# csa-ultrabus-1_0a.net
KiCad netlist of a schematic drawn in EAGLE
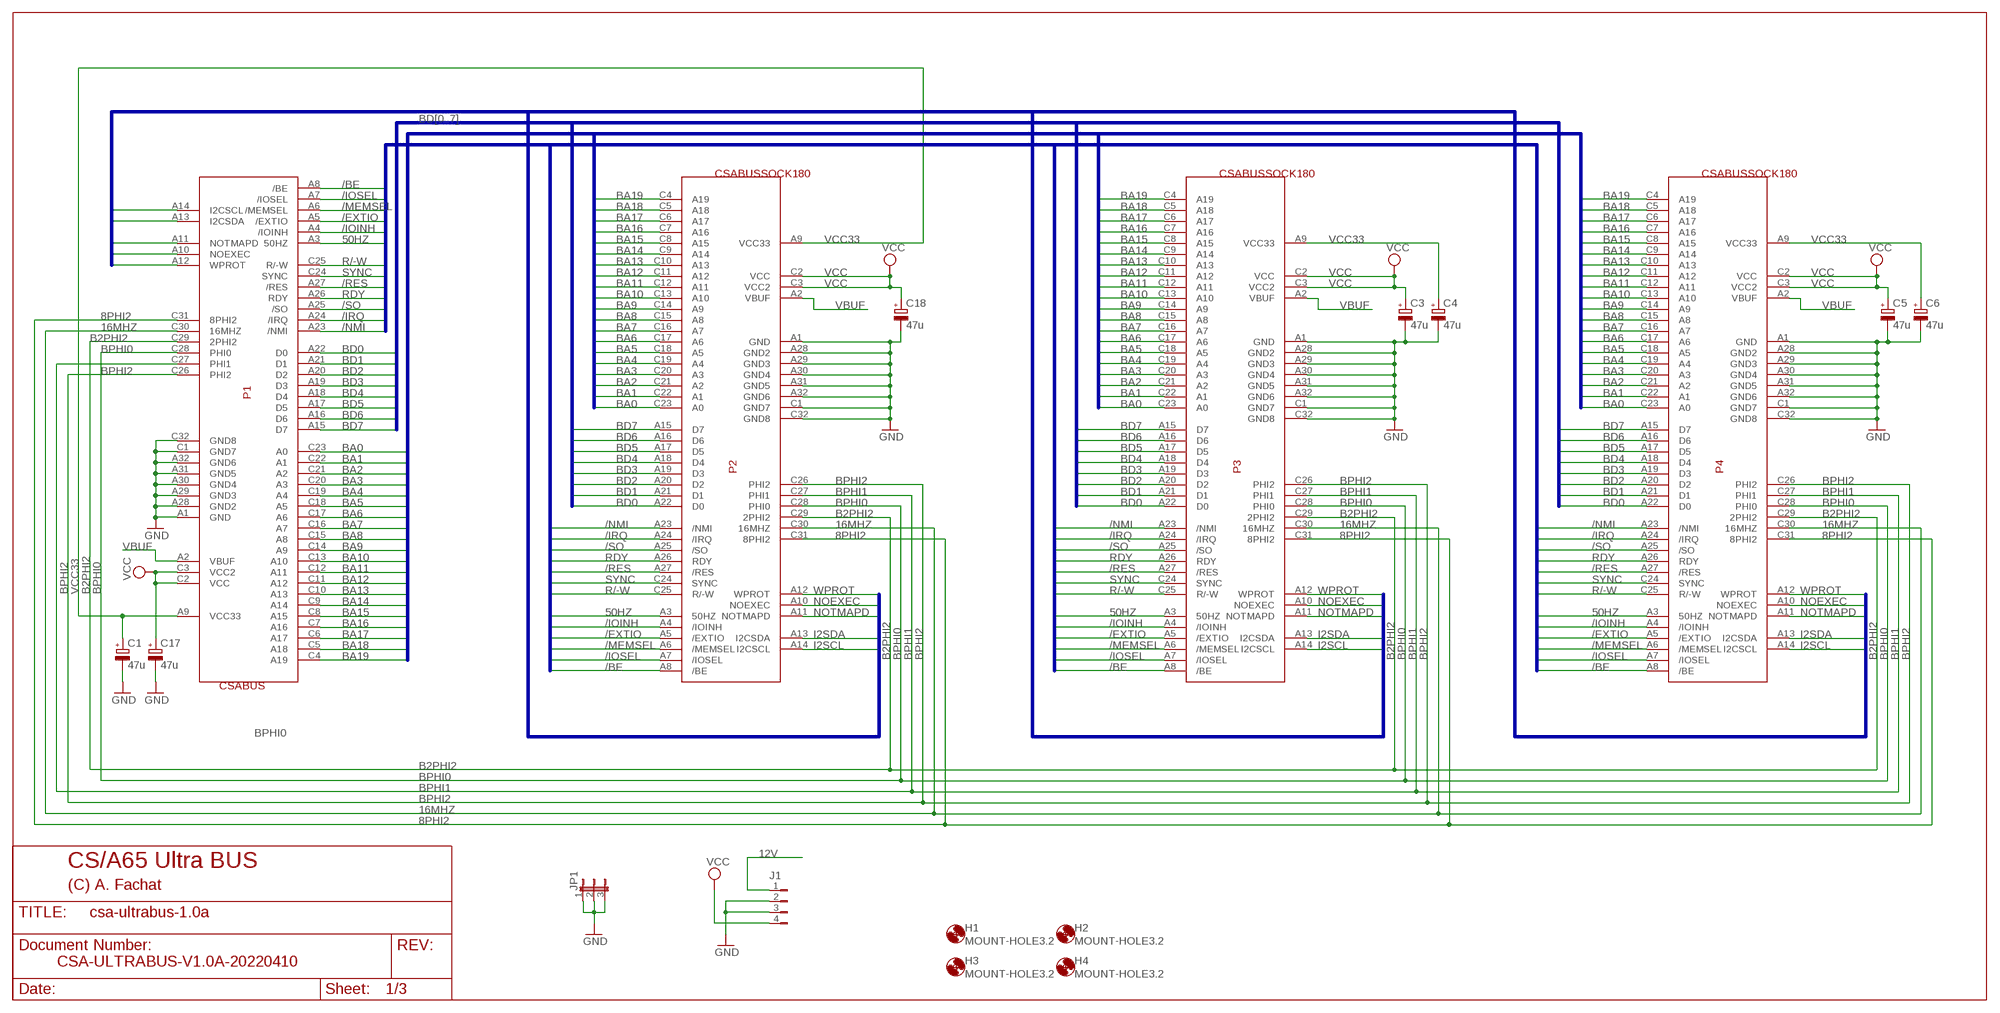
[diagram p0: schematic, sheet 1]
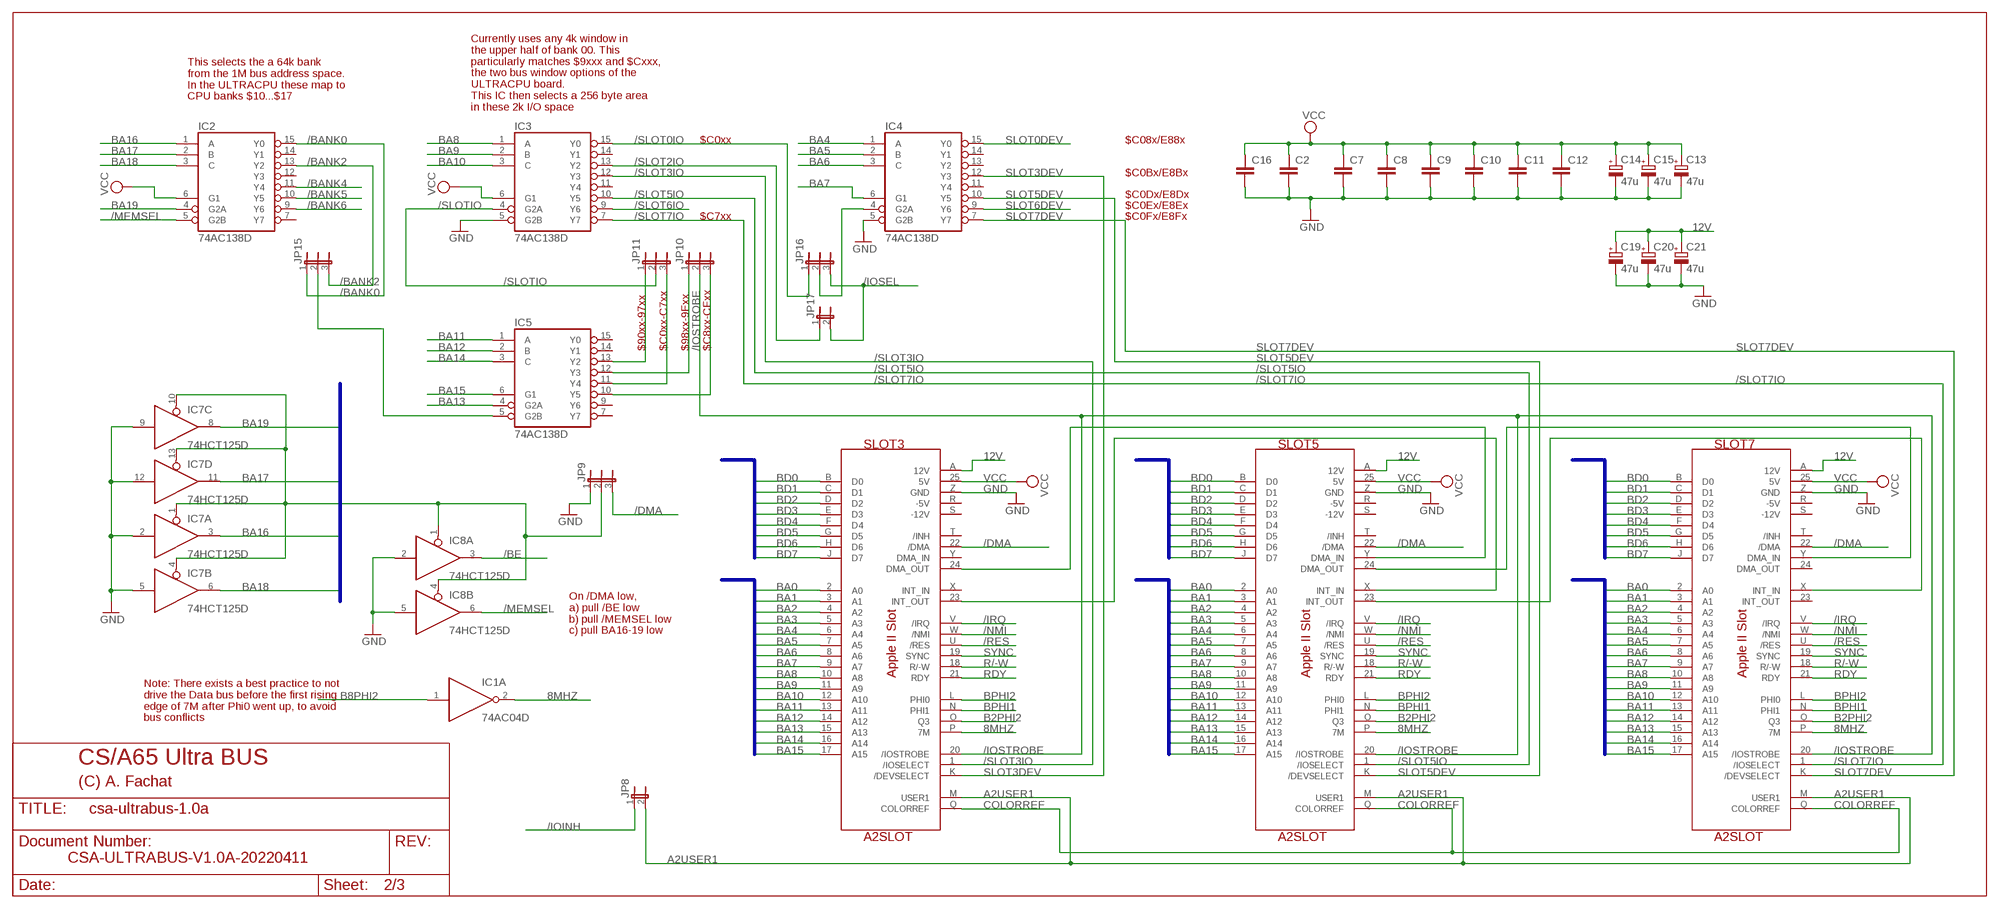
[diagram p1: schematic, sheet 2]
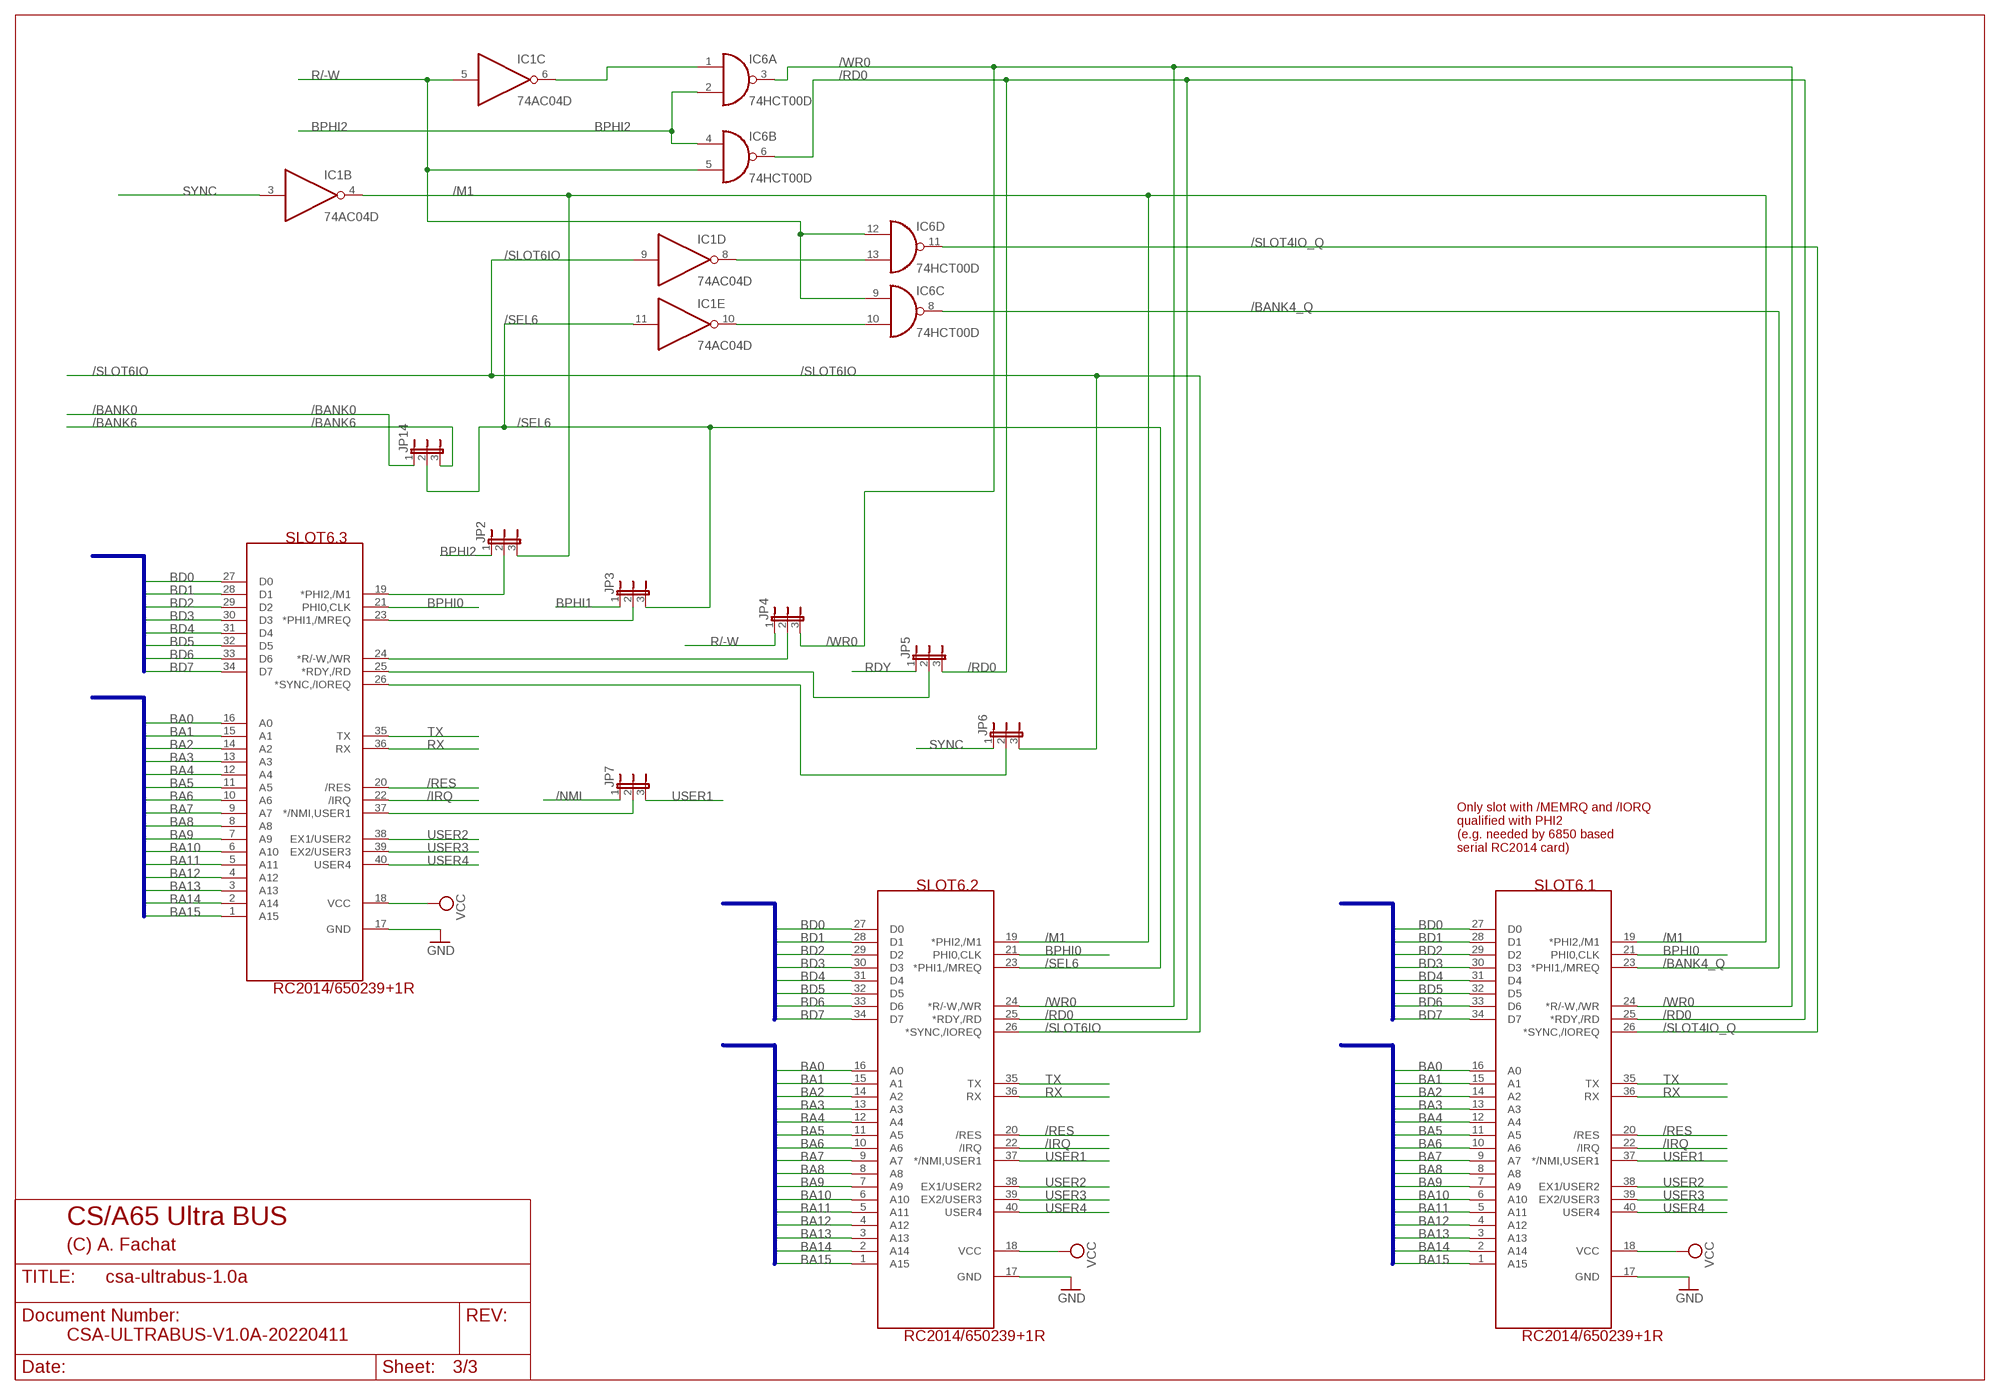
[diagram p2: schematic, sheet 3]

(export (version "E")
  (design (tool "Eeschema 10.0.6"))
  (components
    (comp (ref "C2")
      (value "C-EUC0603")
      (footprint "eagle-import:C0603")
      (libsource (lib "eagle-import") (part "C-EUC0603"))
    )
    (comp (ref "C7")
      (value "C-EUC0603")
      (footprint "eagle-import:C0603")
      (libsource (lib "eagle-import") (part "C-EUC0603"))
    )
    (comp (ref "C8")
      (value "C-EUC0603")
      (footprint "eagle-import:C0603")
      (libsource (lib "eagle-import") (part "C-EUC0603"))
    )
    (comp (ref "C9")
      (value "C-EUC0603")
      (footprint "eagle-import:C0603")
      (libsource (lib "eagle-import") (part "C-EUC0603"))
    )
    (comp (ref "C10")
      (value "C-EUC0603")
      (footprint "eagle-import:C0603")
      (libsource (lib "eagle-import") (part "C-EUC0603"))
    )
    (comp (ref "C11")
      (value "C-EUC0603")
      (footprint "eagle-import:C0603")
      (libsource (lib "eagle-import") (part "C-EUC0603"))
    )
    (comp (ref "C12")
      (value "C-EUC0603")
      (footprint "eagle-import:C0603")
      (libsource (lib "eagle-import") (part "C-EUC0603"))
    )
    (comp (ref "C13")
      (value "47u")
      (footprint "eagle-import:E2,5-5")
      (libsource (lib "eagle-import") (part "CPOL-EUE2.5-5"))
    )
    (comp (ref "C14")
      (value "47u")
      (footprint "eagle-import:E2,5-5")
      (libsource (lib "eagle-import") (part "CPOL-EUE2.5-5"))
    )
    (comp (ref "C15")
      (value "47u")
      (footprint "eagle-import:E2,5-5")
      (libsource (lib "eagle-import") (part "CPOL-EUE2.5-5"))
    )
    (comp (ref "C16")
      (value "C-EUC0603")
      (footprint "eagle-import:C0603")
      (libsource (lib "eagle-import") (part "C-EUC0603"))
    )
    (comp (ref "C19")
      (value "47u")
      (footprint "eagle-import:E2,5-5")
      (libsource (lib "eagle-import") (part "CPOL-EUE2.5-5"))
    )
    (comp (ref "C20")
      (value "47u")
      (footprint "eagle-import:E2,5-5")
      (libsource (lib "eagle-import") (part "CPOL-EUE2.5-5"))
    )
    (comp (ref "C21")
      (value "47u")
      (footprint "eagle-import:E2,5-5")
      (libsource (lib "eagle-import") (part "CPOL-EUE2.5-5"))
    )
    (comp (ref "IC1")
      (value "74AC04D")
      (footprint "eagle-import:SO14")
      (libsource (lib "eagle-import") (part "7404DAC"))
    )
    (comp (ref "IC2")
      (value "74AC138D")
      (footprint "eagle-import:SO16")
      (libsource (lib "eagle-import") (part "74138DAC"))
    )
    (comp (ref "IC3")
      (value "74AC138D")
      (footprint "eagle-import:SO16")
      (libsource (lib "eagle-import") (part "74138DAC"))
    )
    (comp (ref "IC4")
      (value "74AC138D")
      (footprint "eagle-import:SO16")
      (libsource (lib "eagle-import") (part "74138DAC"))
    )
    (comp (ref "IC5")
      (value "74AC138D")
      (footprint "eagle-import:SO16")
      (libsource (lib "eagle-import") (part "74138DAC"))
    )
    (comp (ref "IC7")
      (value "74HCT125D")
      (footprint "eagle-import:SO14")
      (libsource (lib "eagle-import") (part "74125DHCT"))
    )
    (comp (ref "IC8")
      (value "74HCT125D")
      (footprint "eagle-import:SO14")
      (libsource (lib "eagle-import") (part "74125DHCT"))
    )
    (comp (ref "JP8")
      (value "JP1E")
      (footprint "eagle-import:JP1")
      (libsource (lib "eagle-import") (part "JP1E"))
    )
    (comp (ref "JP9")
      (value "JP2E")
      (footprint "eagle-import:JP2")
      (libsource (lib "eagle-import") (part "JP2E"))
    )
    (comp (ref "JP10")
      (value "JP2E")
      (footprint "eagle-import:JP2")
      (libsource (lib "eagle-import") (part "JP2E"))
    )
    (comp (ref "JP11")
      (value "JP2E")
      (footprint "eagle-import:JP2")
      (libsource (lib "eagle-import") (part "JP2E"))
    )
    (comp (ref "JP15")
      (value "JP2E")
      (footprint "eagle-import:JP2")
      (libsource (lib "eagle-import") (part "JP2E"))
    )
    (comp (ref "JP16")
      (value "JP2E")
      (footprint "eagle-import:JP2")
      (libsource (lib "eagle-import") (part "JP2E"))
    )
    (comp (ref "JP17")
      (value "JP1E")
      (footprint "eagle-import:JP1")
      (libsource (lib "eagle-import") (part "JP1E"))
    )
    (comp (ref "SLOT3")
      (value "A2SLOT")
      (footprint "eagle-import:FE100-25")
      (libsource (lib "eagle-import") (part "A2SLOT"))
    )
    (comp (ref "SLOT5")
      (value "A2SLOT")
      (footprint "eagle-import:FE100-25")
      (libsource (lib "eagle-import") (part "A2SLOT"))
    )
    (comp (ref "SLOT7")
      (value "A2SLOT")
      (footprint "eagle-import:FE100-25")
      (libsource (lib "eagle-import") (part "A2SLOT"))
    )
    (comp (ref "IC6")
      (value "74HCT00D")
      (footprint "eagle-import:SO14")
      (libsource (lib "eagle-import") (part "7400DHCT"))
    )
    (comp (ref "JP2")
      (value "JP2E")
      (footprint "eagle-import:JP2")
      (libsource (lib "eagle-import") (part "JP2E"))
    )
    (comp (ref "JP3")
      (value "JP2E")
      (footprint "eagle-import:JP2")
      (libsource (lib "eagle-import") (part "JP2E"))
    )
    (comp (ref "JP4")
      (value "JP2E")
      (footprint "eagle-import:JP2")
      (libsource (lib "eagle-import") (part "JP2E"))
    )
    (comp (ref "JP5")
      (value "JP2E")
      (footprint "eagle-import:JP2")
      (libsource (lib "eagle-import") (part "JP2E"))
    )
    (comp (ref "JP6")
      (value "JP2E")
      (footprint "eagle-import:JP2")
      (libsource (lib "eagle-import") (part "JP2E"))
    )
    (comp (ref "JP7")
      (value "JP2E")
      (footprint "eagle-import:JP2")
      (libsource (lib "eagle-import") (part "JP2E"))
    )
    (comp (ref "JP14")
      (value "JP2E")
      (footprint "eagle-import:JP2")
      (libsource (lib "eagle-import") (part "JP2E"))
    )
    (comp (ref "SLOT6.1")
      (value "RC2014/650239+1R")
      (footprint "eagle-import:SIL39+1R")
      (libsource (lib "eagle-import") (part "RC2014/650239+1R"))
    )
    (comp (ref "SLOT6.2")
      (value "RC2014/650239+1R")
      (footprint "eagle-import:SIL39+1R")
      (libsource (lib "eagle-import") (part "RC2014/650239+1R"))
    )
    (comp (ref "SLOT6.3")
      (value "RC2014/650239+1R")
      (footprint "eagle-import:SIL39+1R")
      (libsource (lib "eagle-import") (part "RC2014/650239+1R"))
    )
    (comp (ref "C1")
      (value "47u")
      (footprint "eagle-import:E2,5-5")
      (libsource (lib "eagle-import") (part "CPOL-EUE2.5-5"))
    )
    (comp (ref "C3")
      (value "47u")
      (footprint "eagle-import:E2,5-5")
      (libsource (lib "eagle-import") (part "CPOL-EUE2.5-5"))
    )
    (comp (ref "C4")
      (value "47u")
      (footprint "eagle-import:E2,5-5")
      (libsource (lib "eagle-import") (part "CPOL-EUE2.5-5"))
    )
    (comp (ref "C5")
      (value "47u")
      (footprint "eagle-import:E2,5-5")
      (libsource (lib "eagle-import") (part "CPOL-EUE2.5-5"))
    )
    (comp (ref "C6")
      (value "47u")
      (footprint "eagle-import:E2,5-5")
      (libsource (lib "eagle-import") (part "CPOL-EUE2.5-5"))
    )
    (comp (ref "C17")
      (value "47u")
      (footprint "eagle-import:E2,5-5")
      (libsource (lib "eagle-import") (part "CPOL-EUE2.5-5"))
    )
    (comp (ref "C18")
      (value "47u")
      (footprint "eagle-import:E2,5-5")
      (libsource (lib "eagle-import") (part "CPOL-EUE2.5-5"))
    )
    (comp (ref "H1")
      (value "MOUNT-HOLE3.2")
      (footprint "eagle-import:3,2")
      (libsource (lib "eagle-import") (part "MOUNT-HOLE3.2"))
    )
    (comp (ref "H2")
      (value "MOUNT-HOLE3.2")
      (footprint "eagle-import:3,2")
      (libsource (lib "eagle-import") (part "MOUNT-HOLE3.2"))
    )
    (comp (ref "H3")
      (value "MOUNT-HOLE3.2")
      (footprint "eagle-import:3,2")
      (libsource (lib "eagle-import") (part "MOUNT-HOLE3.2"))
    )
    (comp (ref "H4")
      (value "MOUNT-HOLE3.2")
      (footprint "eagle-import:3,2")
      (libsource (lib "eagle-import") (part "MOUNT-HOLE3.2"))
    )
    (comp (ref "J1")
      (value "FLOP-4W827001")
      (footprint "eagle-import:827001")
      (libsource (lib "eagle-import") (part "FLOP-4W827001"))
    )
    (comp (ref "JP1")
      (value "JP2E")
      (footprint "eagle-import:JP2")
      (libsource (lib "eagle-import") (part "JP2E"))
    )
    (comp (ref "P1")
      (value "CSABUS")
      (footprint "eagle-import:CSABUS")
      (libsource (lib "eagle-import") (part "CSABUS"))
    )
    (comp (ref "P2")
      (value "CSABUSSOCK180")
      (footprint "eagle-import:CSABUSSOCK180")
      (libsource (lib "eagle-import") (part "CSABUSSOCK180"))
    )
    (comp (ref "P3")
      (value "CSABUSSOCK180")
      (footprint "eagle-import:CSABUSSOCK180")
      (libsource (lib "eagle-import") (part "CSABUSSOCK180"))
    )
    (comp (ref "P4")
      (value "CSABUSSOCK180")
      (footprint "eagle-import:CSABUSSOCK180")
      (libsource (lib "eagle-import") (part "CSABUSSOCK180"))
    )
  )
  (nets
    (net (code "6") (name "8MHZ") (class "Default")
      (node (ref "IC1") (pin "2") (pinfunction "O_2") (pintype "output"))
      (node (ref "SLOT3") (pin "P") (pinfunction "7M_P") (pintype "bidirectional"))
      (node (ref "SLOT5") (pin "P") (pinfunction "7M_P") (pintype "bidirectional"))
      (node (ref "SLOT7") (pin "P") (pinfunction "7M_P") (pintype "bidirectional"))
    )
    (net (code "7") (name "8PHI2") (class "Default")
      (node (ref "P1") (pin "C31") (pinfunction "8PHI2_C31") (pintype "bidirectional"))
      (node (ref "P2") (pin "C31") (pinfunction "8PHI2_C31") (pintype "bidirectional"))
      (node (ref "P3") (pin "C31") (pinfunction "8PHI2_C31") (pintype "bidirectional"))
      (node (ref "P4") (pin "C31") (pinfunction "8PHI2_C31") (pintype "bidirectional"))
    )
    (net (code "8") (name "12V") (class "Default")
      (node (ref "C19") (pin "+") (pinfunction "+_+") (pintype "passive"))
      (node (ref "C20") (pin "+") (pinfunction "+_+") (pintype "passive"))
      (node (ref "C21") (pin "+") (pinfunction "+_+") (pintype "passive"))
      (node (ref "J1") (pin "1") (pinfunction "1_1") (pintype "passive"))
      (node (ref "SLOT3") (pin "A") (pinfunction "12V_A") (pintype "bidirectional"))
      (node (ref "SLOT5") (pin "A") (pinfunction "12V_A") (pintype "bidirectional"))
      (node (ref "SLOT7") (pin "A") (pinfunction "12V_A") (pintype "bidirectional"))
    )
    (net (code "9") (name "16MHZ") (class "Default")
      (node (ref "P1") (pin "C30") (pinfunction "16MHZ_C30") (pintype "bidirectional"))
      (node (ref "P2") (pin "C30") (pinfunction "16MHZ_C30") (pintype "bidirectional"))
      (node (ref "P3") (pin "C30") (pinfunction "16MHZ_C30") (pintype "bidirectional"))
      (node (ref "P4") (pin "C30") (pinfunction "16MHZ_C30") (pintype "bidirectional"))
    )
    (net (code "10") (name "50HZ") (class "Default")
      (node (ref "P1") (pin "A3") (pinfunction "50HZ_A3") (pintype "bidirectional"))
      (node (ref "P2") (pin "A3") (pinfunction "50HZ_A3") (pintype "bidirectional"))
      (node (ref "P3") (pin "A3") (pinfunction "50HZ_A3") (pintype "bidirectional"))
      (node (ref "P4") (pin "A3") (pinfunction "50HZ_A3") (pintype "bidirectional"))
    )
    (net (code "11") (name "A2USER1") (class "Default")
      (node (ref "JP8") (pin "2") (pinfunction "2_2") (pintype "passive"))
      (node (ref "SLOT3") (pin "M") (pinfunction "USER1_M") (pintype "bidirectional"))
      (node (ref "SLOT5") (pin "M") (pinfunction "USER1_M") (pintype "bidirectional"))
      (node (ref "SLOT7") (pin "M") (pinfunction "USER1_M") (pintype "bidirectional"))
    )
    (net (code "12") (name "B2PHI2") (class "Default")
      (node (ref "P1") (pin "C29") (pinfunction "2PHI2_C29") (pintype "bidirectional"))
      (node (ref "P2") (pin "C29") (pinfunction "2PHI2_C29") (pintype "bidirectional"))
      (node (ref "P3") (pin "C29") (pinfunction "2PHI2_C29") (pintype "bidirectional"))
      (node (ref "P4") (pin "C29") (pinfunction "2PHI2_C29") (pintype "bidirectional"))
      (node (ref "SLOT3") (pin "O") (pinfunction "Q3_O") (pintype "bidirectional"))
      (node (ref "SLOT5") (pin "O") (pinfunction "Q3_O") (pintype "bidirectional"))
      (node (ref "SLOT7") (pin "O") (pinfunction "Q3_O") (pintype "bidirectional"))
    )
    (net (code "13") (name "B8PHI2") (class "Default")
      (node (ref "IC1") (pin "1") (pinfunction "I_1") (pintype "input"))
    )
    (net (code "14") (name "BA0") (class "Default")
      (node (ref "P1") (pin "C23") (pinfunction "A0_C23") (pintype "bidirectional"))
      (node (ref "P2") (pin "C23") (pinfunction "A0_C23") (pintype "bidirectional"))
      (node (ref "P3") (pin "C23") (pinfunction "A0_C23") (pintype "bidirectional"))
      (node (ref "P4") (pin "C23") (pinfunction "A0_C23") (pintype "bidirectional"))
      (node (ref "SLOT3") (pin "2") (pinfunction "A0_2") (pintype "bidirectional"))
      (node (ref "SLOT5") (pin "2") (pinfunction "A0_2") (pintype "bidirectional"))
      (node (ref "SLOT6.1") (pin "16") (pinfunction "A0_16") (pintype "bidirectional"))
      (node (ref "SLOT6.2") (pin "16") (pinfunction "A0_16") (pintype "bidirectional"))
      (node (ref "SLOT6.3") (pin "16") (pinfunction "A0_16") (pintype "bidirectional"))
      (node (ref "SLOT7") (pin "2") (pinfunction "A0_2") (pintype "bidirectional"))
    )
    (net (code "15") (name "BA1") (class "Default")
      (node (ref "P1") (pin "C22") (pinfunction "A1_C22") (pintype "bidirectional"))
      (node (ref "P2") (pin "C22") (pinfunction "A1_C22") (pintype "bidirectional"))
      (node (ref "P3") (pin "C22") (pinfunction "A1_C22") (pintype "bidirectional"))
      (node (ref "P4") (pin "C22") (pinfunction "A1_C22") (pintype "bidirectional"))
      (node (ref "SLOT3") (pin "3") (pinfunction "A1_3") (pintype "bidirectional"))
      (node (ref "SLOT5") (pin "3") (pinfunction "A1_3") (pintype "bidirectional"))
      (node (ref "SLOT6.1") (pin "15") (pinfunction "A1_15") (pintype "bidirectional"))
      (node (ref "SLOT6.2") (pin "15") (pinfunction "A1_15") (pintype "bidirectional"))
      (node (ref "SLOT6.3") (pin "15") (pinfunction "A1_15") (pintype "bidirectional"))
      (node (ref "SLOT7") (pin "3") (pinfunction "A1_3") (pintype "bidirectional"))
    )
    (net (code "16") (name "BA2") (class "Default")
      (node (ref "P1") (pin "C21") (pinfunction "A2_C21") (pintype "bidirectional"))
      (node (ref "P2") (pin "C21") (pinfunction "A2_C21") (pintype "bidirectional"))
      (node (ref "P3") (pin "C21") (pinfunction "A2_C21") (pintype "bidirectional"))
      (node (ref "P4") (pin "C21") (pinfunction "A2_C21") (pintype "bidirectional"))
      (node (ref "SLOT3") (pin "4") (pinfunction "A2_4") (pintype "bidirectional"))
      (node (ref "SLOT5") (pin "4") (pinfunction "A2_4") (pintype "bidirectional"))
      (node (ref "SLOT6.1") (pin "14") (pinfunction "A2_14") (pintype "bidirectional"))
      (node (ref "SLOT6.2") (pin "14") (pinfunction "A2_14") (pintype "bidirectional"))
      (node (ref "SLOT6.3") (pin "14") (pinfunction "A2_14") (pintype "bidirectional"))
      (node (ref "SLOT7") (pin "4") (pinfunction "A2_4") (pintype "bidirectional"))
    )
    (net (code "17") (name "BA3") (class "Default")
      (node (ref "P1") (pin "C20") (pinfunction "A3_C20") (pintype "bidirectional"))
      (node (ref "P2") (pin "C20") (pinfunction "A3_C20") (pintype "bidirectional"))
      (node (ref "P3") (pin "C20") (pinfunction "A3_C20") (pintype "bidirectional"))
      (node (ref "P4") (pin "C20") (pinfunction "A3_C20") (pintype "bidirectional"))
      (node (ref "SLOT3") (pin "5") (pinfunction "A3_5") (pintype "bidirectional"))
      (node (ref "SLOT5") (pin "5") (pinfunction "A3_5") (pintype "bidirectional"))
      (node (ref "SLOT6.1") (pin "13") (pinfunction "A3_13") (pintype "bidirectional"))
      (node (ref "SLOT6.2") (pin "13") (pinfunction "A3_13") (pintype "bidirectional"))
      (node (ref "SLOT6.3") (pin "13") (pinfunction "A3_13") (pintype "bidirectional"))
      (node (ref "SLOT7") (pin "5") (pinfunction "A3_5") (pintype "bidirectional"))
    )
    (net (code "18") (name "BA4") (class "Default")
      (node (ref "IC4") (pin "1") (pinfunction "A_1") (pintype "input"))
      (node (ref "P1") (pin "C19") (pinfunction "A4_C19") (pintype "bidirectional"))
      (node (ref "P2") (pin "C19") (pinfunction "A4_C19") (pintype "bidirectional"))
      (node (ref "P3") (pin "C19") (pinfunction "A4_C19") (pintype "bidirectional"))
      (node (ref "P4") (pin "C19") (pinfunction "A4_C19") (pintype "bidirectional"))
      (node (ref "SLOT3") (pin "6") (pinfunction "A4_6") (pintype "bidirectional"))
      (node (ref "SLOT5") (pin "6") (pinfunction "A4_6") (pintype "bidirectional"))
      (node (ref "SLOT6.1") (pin "12") (pinfunction "A4_12") (pintype "bidirectional"))
      (node (ref "SLOT6.2") (pin "12") (pinfunction "A4_12") (pintype "bidirectional"))
      (node (ref "SLOT6.3") (pin "12") (pinfunction "A4_12") (pintype "bidirectional"))
      (node (ref "SLOT7") (pin "6") (pinfunction "A4_6") (pintype "bidirectional"))
    )
    (net (code "19") (name "BA5") (class "Default")
      (node (ref "IC4") (pin "2") (pinfunction "B_2") (pintype "input"))
      (node (ref "P1") (pin "C18") (pinfunction "A5_C18") (pintype "bidirectional"))
      (node (ref "P2") (pin "C18") (pinfunction "A5_C18") (pintype "bidirectional"))
      (node (ref "P3") (pin "C18") (pinfunction "A5_C18") (pintype "bidirectional"))
      (node (ref "P4") (pin "C18") (pinfunction "A5_C18") (pintype "bidirectional"))
      (node (ref "SLOT3") (pin "7") (pinfunction "A5_7") (pintype "bidirectional"))
      (node (ref "SLOT5") (pin "7") (pinfunction "A5_7") (pintype "bidirectional"))
      (node (ref "SLOT6.1") (pin "11") (pinfunction "A5_11") (pintype "bidirectional"))
      (node (ref "SLOT6.2") (pin "11") (pinfunction "A5_11") (pintype "bidirectional"))
      (node (ref "SLOT6.3") (pin "11") (pinfunction "A5_11") (pintype "bidirectional"))
      (node (ref "SLOT7") (pin "7") (pinfunction "A5_7") (pintype "bidirectional"))
    )
    (net (code "20") (name "BA6") (class "Default")
      (node (ref "IC4") (pin "3") (pinfunction "C_3") (pintype "input"))
      (node (ref "P1") (pin "C17") (pinfunction "A6_C17") (pintype "bidirectional"))
      (node (ref "P2") (pin "C17") (pinfunction "A6_C17") (pintype "bidirectional"))
      (node (ref "P3") (pin "C17") (pinfunction "A6_C17") (pintype "bidirectional"))
      (node (ref "P4") (pin "C17") (pinfunction "A6_C17") (pintype "bidirectional"))
      (node (ref "SLOT3") (pin "8") (pinfunction "A6_8") (pintype "bidirectional"))
      (node (ref "SLOT5") (pin "8") (pinfunction "A6_8") (pintype "bidirectional"))
      (node (ref "SLOT6.1") (pin "10") (pinfunction "A6_10") (pintype "bidirectional"))
      (node (ref "SLOT6.2") (pin "10") (pinfunction "A6_10") (pintype "bidirectional"))
      (node (ref "SLOT6.3") (pin "10") (pinfunction "A6_10") (pintype "bidirectional"))
      (node (ref "SLOT7") (pin "8") (pinfunction "A6_8") (pintype "bidirectional"))
    )
    (net (code "21") (name "BA7") (class "Default")
      (node (ref "IC4") (pin "6") (pinfunction "G1_6") (pintype "input"))
      (node (ref "P1") (pin "C16") (pinfunction "A7_C16") (pintype "bidirectional"))
      (node (ref "P2") (pin "C16") (pinfunction "A7_C16") (pintype "bidirectional"))
      (node (ref "P3") (pin "C16") (pinfunction "A7_C16") (pintype "bidirectional"))
      (node (ref "P4") (pin "C16") (pinfunction "A7_C16") (pintype "bidirectional"))
      (node (ref "SLOT3") (pin "9") (pinfunction "A7_9") (pintype "bidirectional"))
      (node (ref "SLOT5") (pin "9") (pinfunction "A7_9") (pintype "bidirectional"))
      (node (ref "SLOT6.1") (pin "9") (pinfunction "A7_9") (pintype "bidirectional"))
      (node (ref "SLOT6.2") (pin "9") (pinfunction "A7_9") (pintype "bidirectional"))
      (node (ref "SLOT6.3") (pin "9") (pinfunction "A7_9") (pintype "bidirectional"))
      (node (ref "SLOT7") (pin "9") (pinfunction "A7_9") (pintype "bidirectional"))
    )
    (net (code "22") (name "BA8") (class "Default")
      (node (ref "IC3") (pin "1") (pinfunction "A_1") (pintype "input"))
      (node (ref "P1") (pin "C15") (pinfunction "A8_C15") (pintype "bidirectional"))
      (node (ref "P2") (pin "C15") (pinfunction "A8_C15") (pintype "bidirectional"))
      (node (ref "P3") (pin "C15") (pinfunction "A8_C15") (pintype "bidirectional"))
      (node (ref "P4") (pin "C15") (pinfunction "A8_C15") (pintype "bidirectional"))
      (node (ref "SLOT3") (pin "10") (pinfunction "A8_10") (pintype "bidirectional"))
      (node (ref "SLOT5") (pin "10") (pinfunction "A8_10") (pintype "bidirectional"))
      (node (ref "SLOT6.1") (pin "8") (pinfunction "A8_8") (pintype "bidirectional"))
      (node (ref "SLOT6.2") (pin "8") (pinfunction "A8_8") (pintype "bidirectional"))
      (node (ref "SLOT6.3") (pin "8") (pinfunction "A8_8") (pintype "bidirectional"))
      (node (ref "SLOT7") (pin "10") (pinfunction "A8_10") (pintype "bidirectional"))
    )
    (net (code "23") (name "BA9") (class "Default")
      (node (ref "IC3") (pin "2") (pinfunction "B_2") (pintype "input"))
      (node (ref "P1") (pin "C14") (pinfunction "A9_C14") (pintype "bidirectional"))
      (node (ref "P2") (pin "C14") (pinfunction "A9_C14") (pintype "bidirectional"))
      (node (ref "P3") (pin "C14") (pinfunction "A9_C14") (pintype "bidirectional"))
      (node (ref "P4") (pin "C14") (pinfunction "A9_C14") (pintype "bidirectional"))
      (node (ref "SLOT3") (pin "11") (pinfunction "A9_11") (pintype "bidirectional"))
      (node (ref "SLOT5") (pin "11") (pinfunction "A9_11") (pintype "bidirectional"))
      (node (ref "SLOT6.1") (pin "7") (pinfunction "A9_7") (pintype "bidirectional"))
      (node (ref "SLOT6.2") (pin "7") (pinfunction "A9_7") (pintype "bidirectional"))
      (node (ref "SLOT6.3") (pin "7") (pinfunction "A9_7") (pintype "bidirectional"))
      (node (ref "SLOT7") (pin "11") (pinfunction "A9_11") (pintype "bidirectional"))
    )
    (net (code "24") (name "BA10") (class "Default")
      (node (ref "IC3") (pin "3") (pinfunction "C_3") (pintype "input"))
      (node (ref "P1") (pin "C13") (pinfunction "A10_C13") (pintype "bidirectional"))
      (node (ref "P2") (pin "C13") (pinfunction "A10_C13") (pintype "bidirectional"))
      (node (ref "P3") (pin "C13") (pinfunction "A10_C13") (pintype "bidirectional"))
      (node (ref "P4") (pin "C13") (pinfunction "A10_C13") (pintype "bidirectional"))
      (node (ref "SLOT3") (pin "12") (pinfunction "A10_12") (pintype "bidirectional"))
      (node (ref "SLOT5") (pin "12") (pinfunction "A10_12") (pintype "bidirectional"))
      (node (ref "SLOT6.1") (pin "6") (pinfunction "A10_6") (pintype "bidirectional"))
      (node (ref "SLOT6.2") (pin "6") (pinfunction "A10_6") (pintype "bidirectional"))
      (node (ref "SLOT6.3") (pin "6") (pinfunction "A10_6") (pintype "bidirectional"))
      (node (ref "SLOT7") (pin "12") (pinfunction "A10_12") (pintype "bidirectional"))
    )
    (net (code "25") (name "BA11") (class "Default")
      (node (ref "IC5") (pin "1") (pinfunction "A_1") (pintype "input"))
      (node (ref "P1") (pin "C12") (pinfunction "A11_C12") (pintype "bidirectional"))
      (node (ref "P2") (pin "C12") (pinfunction "A11_C12") (pintype "bidirectional"))
      (node (ref "P3") (pin "C12") (pinfunction "A11_C12") (pintype "bidirectional"))
      (node (ref "P4") (pin "C12") (pinfunction "A11_C12") (pintype "bidirectional"))
      (node (ref "SLOT3") (pin "13") (pinfunction "A11_13") (pintype "bidirectional"))
      (node (ref "SLOT5") (pin "13") (pinfunction "A11_13") (pintype "bidirectional"))
      (node (ref "SLOT6.1") (pin "5") (pinfunction "A11_5") (pintype "bidirectional"))
      (node (ref "SLOT6.2") (pin "5") (pinfunction "A11_5") (pintype "bidirectional"))
      (node (ref "SLOT6.3") (pin "5") (pinfunction "A11_5") (pintype "bidirectional"))
      (node (ref "SLOT7") (pin "13") (pinfunction "A11_13") (pintype "bidirectional"))
    )
    (net (code "26") (name "BA12") (class "Default")
      (node (ref "IC5") (pin "2") (pinfunction "B_2") (pintype "input"))
      (node (ref "P1") (pin "C11") (pinfunction "A12_C11") (pintype "bidirectional"))
      (node (ref "P2") (pin "C11") (pinfunction "A12_C11") (pintype "bidirectional"))
      (node (ref "P3") (pin "C11") (pinfunction "A12_C11") (pintype "bidirectional"))
      (node (ref "P4") (pin "C11") (pinfunction "A12_C11") (pintype "bidirectional"))
      (node (ref "SLOT3") (pin "14") (pinfunction "A12_14") (pintype "bidirectional"))
      (node (ref "SLOT5") (pin "14") (pinfunction "A12_14") (pintype "bidirectional"))
      (node (ref "SLOT6.1") (pin "4") (pinfunction "A12_4") (pintype "bidirectional"))
      (node (ref "SLOT6.2") (pin "4") (pinfunction "A12_4") (pintype "bidirectional"))
      (node (ref "SLOT6.3") (pin "4") (pinfunction "A12_4") (pintype "bidirectional"))
      (node (ref "SLOT7") (pin "14") (pinfunction "A12_14") (pintype "bidirectional"))
    )
    (net (code "27") (name "BA13") (class "Default")
      (node (ref "IC5") (pin "4") (pinfunction "G2A_4") (pintype "input"))
      (node (ref "P1") (pin "C10") (pinfunction "A13_C10") (pintype "bidirectional"))
      (node (ref "P2") (pin "C10") (pinfunction "A13_C10") (pintype "bidirectional"))
      (node (ref "P3") (pin "C10") (pinfunction "A13_C10") (pintype "bidirectional"))
      (node (ref "P4") (pin "C10") (pinfunction "A13_C10") (pintype "bidirectional"))
      (node (ref "SLOT3") (pin "15") (pinfunction "A13_15") (pintype "bidirectional"))
      (node (ref "SLOT5") (pin "15") (pinfunction "A13_15") (pintype "bidirectional"))
      (node (ref "SLOT6.1") (pin "3") (pinfunction "A13_3") (pintype "bidirectional"))
      (node (ref "SLOT6.2") (pin "3") (pinfunction "A13_3") (pintype "bidirectional"))
      (node (ref "SLOT6.3") (pin "3") (pinfunction "A13_3") (pintype "bidirectional"))
      (node (ref "SLOT7") (pin "15") (pinfunction "A13_15") (pintype "bidirectional"))
    )
    (net (code "28") (name "BA14") (class "Default")
      (node (ref "IC5") (pin "3") (pinfunction "C_3") (pintype "input"))
      (node (ref "P1") (pin "C9") (pinfunction "A14_C9") (pintype "bidirectional"))
      (node (ref "P2") (pin "C9") (pinfunction "A14_C9") (pintype "bidirectional"))
      (node (ref "P3") (pin "C9") (pinfunction "A14_C9") (pintype "bidirectional"))
      (node (ref "P4") (pin "C9") (pinfunction "A14_C9") (pintype "bidirectional"))
      (node (ref "SLOT3") (pin "16") (pinfunction "A14_16") (pintype "bidirectional"))
      (node (ref "SLOT5") (pin "16") (pinfunction "A14_16") (pintype "bidirectional"))
      (node (ref "SLOT6.1") (pin "2") (pinfunction "A14_2") (pintype "bidirectional"))
      (node (ref "SLOT6.2") (pin "2") (pinfunction "A14_2") (pintype "bidirectional"))
      (node (ref "SLOT6.3") (pin "2") (pinfunction "A14_2") (pintype "bidirectional"))
      (node (ref "SLOT7") (pin "16") (pinfunction "A14_16") (pintype "bidirectional"))
    )
    (net (code "29") (name "BA15") (class "Default")
      (node (ref "IC5") (pin "6") (pinfunction "G1_6") (pintype "input"))
      (node (ref "P1") (pin "C8") (pinfunction "A15_C8") (pintype "bidirectional"))
      (node (ref "P2") (pin "C8") (pinfunction "A15_C8") (pintype "bidirectional"))
      (node (ref "P3") (pin "C8") (pinfunction "A15_C8") (pintype "bidirectional"))
      (node (ref "P4") (pin "C8") (pinfunction "A15_C8") (pintype "bidirectional"))
      (node (ref "SLOT3") (pin "17") (pinfunction "A15_17") (pintype "bidirectional"))
      (node (ref "SLOT5") (pin "17") (pinfunction "A15_17") (pintype "bidirectional"))
      (node (ref "SLOT6.1") (pin "1") (pinfunction "A15_1") (pintype "bidirectional"))
      (node (ref "SLOT6.2") (pin "1") (pinfunction "A15_1") (pintype "bidirectional"))
      (node (ref "SLOT6.3") (pin "1") (pinfunction "A15_1") (pintype "bidirectional"))
      (node (ref "SLOT7") (pin "17") (pinfunction "A15_17") (pintype "bidirectional"))
    )
    (net (code "30") (name "BA16") (class "Default")
      (node (ref "IC2") (pin "1") (pinfunction "A_1") (pintype "input"))
      (node (ref "IC7") (pin "3") (pinfunction "O_3") (pintype "tri_state"))
      (node (ref "P1") (pin "C7") (pinfunction "A16_C7") (pintype "bidirectional"))
      (node (ref "P2") (pin "C7") (pinfunction "A16_C7") (pintype "bidirectional"))
      (node (ref "P3") (pin "C7") (pinfunction "A16_C7") (pintype "bidirectional"))
      (node (ref "P4") (pin "C7") (pinfunction "A16_C7") (pintype "bidirectional"))
    )
    (net (code "31") (name "BA17") (class "Default")
      (node (ref "IC2") (pin "2") (pinfunction "B_2") (pintype "input"))
      (node (ref "IC7") (pin "11") (pinfunction "O_11") (pintype "tri_state"))
      (node (ref "P1") (pin "C6") (pinfunction "A17_C6") (pintype "bidirectional"))
      (node (ref "P2") (pin "C6") (pinfunction "A17_C6") (pintype "bidirectional"))
      (node (ref "P3") (pin "C6") (pinfunction "A17_C6") (pintype "bidirectional"))
      (node (ref "P4") (pin "C6") (pinfunction "A17_C6") (pintype "bidirectional"))
    )
    (net (code "32") (name "BA18") (class "Default")
      (node (ref "IC2") (pin "3") (pinfunction "C_3") (pintype "input"))
      (node (ref "IC7") (pin "6") (pinfunction "O_6") (pintype "tri_state"))
      (node (ref "P1") (pin "C5") (pinfunction "A18_C5") (pintype "bidirectional"))
      (node (ref "P2") (pin "C5") (pinfunction "A18_C5") (pintype "bidirectional"))
      (node (ref "P3") (pin "C5") (pinfunction "A18_C5") (pintype "bidirectional"))
      (node (ref "P4") (pin "C5") (pinfunction "A18_C5") (pintype "bidirectional"))
    )
    (net (code "33") (name "BA19") (class "Default")
      (node (ref "IC2") (pin "4") (pinfunction "G2A_4") (pintype "input"))
      (node (ref "IC7") (pin "8") (pinfunction "O_8") (pintype "tri_state"))
      (node (ref "P1") (pin "C4") (pinfunction "A19_C4") (pintype "bidirectional"))
      (node (ref "P2") (pin "C4") (pinfunction "A19_C4") (pintype "bidirectional"))
      (node (ref "P3") (pin "C4") (pinfunction "A19_C4") (pintype "bidirectional"))
      (node (ref "P4") (pin "C4") (pinfunction "A19_C4") (pintype "bidirectional"))
    )
    (net (code "34") (name "BD0") (class "Default")
      (node (ref "P1") (pin "A22") (pinfunction "D0_A22") (pintype "bidirectional"))
      (node (ref "P2") (pin "A22") (pinfunction "D0_A22") (pintype "bidirectional"))
      (node (ref "P3") (pin "A22") (pinfunction "D0_A22") (pintype "bidirectional"))
      (node (ref "P4") (pin "A22") (pinfunction "D0_A22") (pintype "bidirectional"))
      (node (ref "SLOT3") (pin "B") (pinfunction "D0_B") (pintype "bidirectional"))
      (node (ref "SLOT5") (pin "B") (pinfunction "D0_B") (pintype "bidirectional"))
      (node (ref "SLOT6.1") (pin "27") (pinfunction "D0_27") (pintype "bidirectional"))
      (node (ref "SLOT6.2") (pin "27") (pinfunction "D0_27") (pintype "bidirectional"))
      (node (ref "SLOT6.3") (pin "27") (pinfunction "D0_27") (pintype "bidirectional"))
      (node (ref "SLOT7") (pin "B") (pinfunction "D0_B") (pintype "bidirectional"))
    )
    (net (code "35") (name "BD1") (class "Default")
      (node (ref "P1") (pin "A21") (pinfunction "D1_A21") (pintype "bidirectional"))
      (node (ref "P2") (pin "A21") (pinfunction "D1_A21") (pintype "bidirectional"))
      (node (ref "P3") (pin "A21") (pinfunction "D1_A21") (pintype "bidirectional"))
      (node (ref "P4") (pin "A21") (pinfunction "D1_A21") (pintype "bidirectional"))
      (node (ref "SLOT3") (pin "C") (pinfunction "D1_C") (pintype "bidirectional"))
      (node (ref "SLOT5") (pin "C") (pinfunction "D1_C") (pintype "bidirectional"))
      (node (ref "SLOT6.1") (pin "28") (pinfunction "D1_28") (pintype "bidirectional"))
      (node (ref "SLOT6.2") (pin "28") (pinfunction "D1_28") (pintype "bidirectional"))
      (node (ref "SLOT6.3") (pin "28") (pinfunction "D1_28") (pintype "bidirectional"))
      (node (ref "SLOT7") (pin "C") (pinfunction "D1_C") (pintype "bidirectional"))
    )
    (net (code "36") (name "BD2") (class "Default")
      (node (ref "P1") (pin "A20") (pinfunction "D2_A20") (pintype "bidirectional"))
      (node (ref "P2") (pin "A20") (pinfunction "D2_A20") (pintype "bidirectional"))
      (node (ref "P3") (pin "A20") (pinfunction "D2_A20") (pintype "bidirectional"))
      (node (ref "P4") (pin "A20") (pinfunction "D2_A20") (pintype "bidirectional"))
      (node (ref "SLOT3") (pin "D") (pinfunction "D2_D") (pintype "bidirectional"))
      (node (ref "SLOT5") (pin "D") (pinfunction "D2_D") (pintype "bidirectional"))
      (node (ref "SLOT6.1") (pin "29") (pinfunction "D2_29") (pintype "bidirectional"))
      (node (ref "SLOT6.2") (pin "29") (pinfunction "D2_29") (pintype "bidirectional"))
      (node (ref "SLOT6.3") (pin "29") (pinfunction "D2_29") (pintype "bidirectional"))
      (node (ref "SLOT7") (pin "D") (pinfunction "D2_D") (pintype "bidirectional"))
    )
    (net (code "37") (name "BD3") (class "Default")
      (node (ref "P1") (pin "A19") (pinfunction "D3_A19") (pintype "bidirectional"))
      (node (ref "P2") (pin "A19") (pinfunction "D3_A19") (pintype "bidirectional"))
      (node (ref "P3") (pin "A19") (pinfunction "D3_A19") (pintype "bidirectional"))
      (node (ref "P4") (pin "A19") (pinfunction "D3_A19") (pintype "bidirectional"))
      (node (ref "SLOT3") (pin "E") (pinfunction "D3_E") (pintype "bidirectional"))
      (node (ref "SLOT5") (pin "E") (pinfunction "D3_E") (pintype "bidirectional"))
      (node (ref "SLOT6.1") (pin "30") (pinfunction "D3_30") (pintype "bidirectional"))
      (node (ref "SLOT6.2") (pin "30") (pinfunction "D3_30") (pintype "bidirectional"))
      (node (ref "SLOT6.3") (pin "30") (pinfunction "D3_30") (pintype "bidirectional"))
      (node (ref "SLOT7") (pin "E") (pinfunction "D3_E") (pintype "bidirectional"))
    )
    (net (code "38") (name "BD4") (class "Default")
      (node (ref "P1") (pin "A18") (pinfunction "D4_A18") (pintype "bidirectional"))
      (node (ref "P2") (pin "A18") (pinfunction "D4_A18") (pintype "bidirectional"))
      (node (ref "P3") (pin "A18") (pinfunction "D4_A18") (pintype "bidirectional"))
      (node (ref "P4") (pin "A18") (pinfunction "D4_A18") (pintype "bidirectional"))
      (node (ref "SLOT3") (pin "F") (pinfunction "D4_F") (pintype "bidirectional"))
      (node (ref "SLOT5") (pin "F") (pinfunction "D4_F") (pintype "bidirectional"))
      (node (ref "SLOT6.1") (pin "31") (pinfunction "D4_31") (pintype "bidirectional"))
      (node (ref "SLOT6.2") (pin "31") (pinfunction "D4_31") (pintype "bidirectional"))
      (node (ref "SLOT6.3") (pin "31") (pinfunction "D4_31") (pintype "bidirectional"))
      (node (ref "SLOT7") (pin "F") (pinfunction "D4_F") (pintype "bidirectional"))
    )
    (net (code "39") (name "BD5") (class "Default")
      (node (ref "P1") (pin "A17") (pinfunction "D5_A17") (pintype "bidirectional"))
      (node (ref "P2") (pin "A17") (pinfunction "D5_A17") (pintype "bidirectional"))
      (node (ref "P3") (pin "A17") (pinfunction "D5_A17") (pintype "bidirectional"))
      (node (ref "P4") (pin "A17") (pinfunction "D5_A17") (pintype "bidirectional"))
      (node (ref "SLOT3") (pin "G") (pinfunction "D5_G") (pintype "bidirectional"))
      (node (ref "SLOT5") (pin "G") (pinfunction "D5_G") (pintype "bidirectional"))
      (node (ref "SLOT6.1") (pin "32") (pinfunction "D5_32") (pintype "bidirectional"))
      (node (ref "SLOT6.2") (pin "32") (pinfunction "D5_32") (pintype "bidirectional"))
      (node (ref "SLOT6.3") (pin "32") (pinfunction "D5_32") (pintype "bidirectional"))
      (node (ref "SLOT7") (pin "G") (pinfunction "D5_G") (pintype "bidirectional"))
    )
    (net (code "40") (name "BD6") (class "Default")
      (node (ref "P1") (pin "A16") (pinfunction "D6_A16") (pintype "bidirectional"))
      (node (ref "P2") (pin "A16") (pinfunction "D6_A16") (pintype "bidirectional"))
      (node (ref "P3") (pin "A16") (pinfunction "D6_A16") (pintype "bidirectional"))
      (node (ref "P4") (pin "A16") (pinfunction "D6_A16") (pintype "bidirectional"))
      (node (ref "SLOT3") (pin "H") (pinfunction "D6_H") (pintype "bidirectional"))
      (node (ref "SLOT5") (pin "H") (pinfunction "D6_H") (pintype "bidirectional"))
      (node (ref "SLOT6.1") (pin "33") (pinfunction "D6_33") (pintype "bidirectional"))
      (node (ref "SLOT6.2") (pin "33") (pinfunction "D6_33") (pintype "bidirectional"))
      (node (ref "SLOT6.3") (pin "33") (pinfunction "D6_33") (pintype "bidirectional"))
      (node (ref "SLOT7") (pin "H") (pinfunction "D6_H") (pintype "bidirectional"))
    )
    (net (code "41") (name "BD7") (class "Default")
      (node (ref "P1") (pin "A15") (pinfunction "D7_A15") (pintype "bidirectional"))
      (node (ref "P2") (pin "A15") (pinfunction "D7_A15") (pintype "bidirectional"))
      (node (ref "P3") (pin "A15") (pinfunction "D7_A15") (pintype "bidirectional"))
      (node (ref "P4") (pin "A15") (pinfunction "D7_A15") (pintype "bidirectional"))
      (node (ref "SLOT3") (pin "J") (pinfunction "D7_J") (pintype "bidirectional"))
      (node (ref "SLOT5") (pin "J") (pinfunction "D7_J") (pintype "bidirectional"))
      (node (ref "SLOT6.1") (pin "34") (pinfunction "D7_34") (pintype "bidirectional"))
      (node (ref "SLOT6.2") (pin "34") (pinfunction "D7_34") (pintype "bidirectional"))
      (node (ref "SLOT6.3") (pin "34") (pinfunction "D7_34") (pintype "bidirectional"))
      (node (ref "SLOT7") (pin "J") (pinfunction "D7_J") (pintype "bidirectional"))
    )
    (net (code "42") (name "BPHI0") (class "Default")
      (node (ref "P1") (pin "C28") (pinfunction "PHI0_C28") (pintype "bidirectional"))
      (node (ref "P2") (pin "C28") (pinfunction "PHI0_C28") (pintype "bidirectional"))
      (node (ref "P3") (pin "C28") (pinfunction "PHI0_C28") (pintype "bidirectional"))
      (node (ref "P4") (pin "C28") (pinfunction "PHI0_C28") (pintype "bidirectional"))
      (node (ref "SLOT6.1") (pin "21") (pinfunction "PHI0,CLK_21") (pintype "bidirectional"))
      (node (ref "SLOT6.2") (pin "21") (pinfunction "PHI0,CLK_21") (pintype "bidirectional"))
      (node (ref "SLOT6.3") (pin "21") (pinfunction "PHI0,CLK_21") (pintype "bidirectional"))
    )
    (net (code "43") (name "BPHI1") (class "Default")
      (node (ref "JP3") (pin "1") (pinfunction "1_1") (pintype "passive"))
      (node (ref "P1") (pin "C27") (pinfunction "PHI1_C27") (pintype "bidirectional"))
      (node (ref "P2") (pin "C27") (pinfunction "PHI1_C27") (pintype "bidirectional"))
      (node (ref "P3") (pin "C27") (pinfunction "PHI1_C27") (pintype "bidirectional"))
      (node (ref "P4") (pin "C27") (pinfunction "PHI1_C27") (pintype "bidirectional"))
      (node (ref "SLOT3") (pin "N") (pinfunction "PHI1_N") (pintype "bidirectional"))
      (node (ref "SLOT5") (pin "N") (pinfunction "PHI1_N") (pintype "bidirectional"))
      (node (ref "SLOT7") (pin "N") (pinfunction "PHI1_N") (pintype "bidirectional"))
    )
    (net (code "44") (name "BPHI2") (class "Default")
      (node (ref "IC6") (pin "2") (pinfunction "I1_2") (pintype "input"))
      (node (ref "IC6") (pin "4") (pinfunction "I0_4") (pintype "input"))
      (node (ref "JP2") (pin "1") (pinfunction "1_1") (pintype "passive"))
      (node (ref "P1") (pin "C26") (pinfunction "PHI2_C26") (pintype "bidirectional"))
      (node (ref "P2") (pin "C26") (pinfunction "PHI2_C26") (pintype "bidirectional"))
      (node (ref "P3") (pin "C26") (pinfunction "PHI2_C26") (pintype "bidirectional"))
      (node (ref "P4") (pin "C26") (pinfunction "PHI2_C26") (pintype "bidirectional"))
      (node (ref "SLOT3") (pin "L") (pinfunction "PHI0_L") (pintype "bidirectional"))
      (node (ref "SLOT5") (pin "L") (pinfunction "PHI0_L") (pintype "bidirectional"))
      (node (ref "SLOT7") (pin "L") (pinfunction "PHI0_L") (pintype "bidirectional"))
    )
    (net (code "45") (name "COLORREF") (class "Default")
      (node (ref "SLOT3") (pin "Q") (pinfunction "COLORREF_Q") (pintype "bidirectional"))
      (node (ref "SLOT5") (pin "Q") (pinfunction "COLORREF_Q") (pintype "bidirectional"))
      (node (ref "SLOT7") (pin "Q") (pinfunction "COLORREF_Q") (pintype "bidirectional"))
    )
    (net (code "46") (name "GND") (class "Default")
      (node (ref "C1") (pin "-") (pinfunction "-_-") (pintype "passive"))
      (node (ref "C10") (pin "2") (pinfunction "2_2") (pintype "passive"))
      (node (ref "C11") (pin "2") (pinfunction "2_2") (pintype "passive"))
      (node (ref "C12") (pin "2") (pinfunction "2_2") (pintype "passive"))
      (node (ref "C13") (pin "-") (pinfunction "-_-") (pintype "passive"))
      (node (ref "C14") (pin "-") (pinfunction "-_-") (pintype "passive"))
      (node (ref "C15") (pin "-") (pinfunction "-_-") (pintype "passive"))
      (node (ref "C16") (pin "2") (pinfunction "2_2") (pintype "passive"))
      (node (ref "C17") (pin "-") (pinfunction "-_-") (pintype "passive"))
      (node (ref "C18") (pin "-") (pinfunction "-_-") (pintype "passive"))
      (node (ref "C19") (pin "-") (pinfunction "-_-") (pintype "passive"))
      (node (ref "C2") (pin "2") (pinfunction "2_2") (pintype "passive"))
      (node (ref "C20") (pin "-") (pinfunction "-_-") (pintype "passive"))
      (node (ref "C21") (pin "-") (pinfunction "-_-") (pintype "passive"))
      (node (ref "C3") (pin "-") (pinfunction "-_-") (pintype "passive"))
      (node (ref "C4") (pin "-") (pinfunction "-_-") (pintype "passive"))
      (node (ref "C5") (pin "-") (pinfunction "-_-") (pintype "passive"))
      (node (ref "C6") (pin "-") (pinfunction "-_-") (pintype "passive"))
      (node (ref "C7") (pin "2") (pinfunction "2_2") (pintype "passive"))
      (node (ref "C8") (pin "2") (pinfunction "2_2") (pintype "passive"))
      (node (ref "C9") (pin "2") (pinfunction "2_2") (pintype "passive"))
      (node (ref "IC3") (pin "5") (pinfunction "G2B_5") (pintype "input"))
      (node (ref "IC4") (pin "5") (pinfunction "G2B_5") (pintype "input"))
      (node (ref "IC7") (pin "12") (pinfunction "I_12") (pintype "input"))
      (node (ref "IC7") (pin "2") (pinfunction "I_2") (pintype "input"))
      (node (ref "IC7") (pin "5") (pinfunction "I_5") (pintype "input"))
      (node (ref "IC7") (pin "9") (pinfunction "I_9") (pintype "input"))
      (node (ref "IC8") (pin "2") (pinfunction "I_2") (pintype "input"))
      (node (ref "IC8") (pin "5") (pinfunction "I_5") (pintype "input"))
      (node (ref "J1") (pin "2") (pinfunction "2_2") (pintype "passive"))
      (node (ref "J1") (pin "3") (pinfunction "3_3") (pintype "passive"))
      (node (ref "JP1") (pin "1") (pinfunction "1_1") (pintype "passive"))
      (node (ref "JP1") (pin "2") (pinfunction "2_2") (pintype "passive"))
      (node (ref "JP1") (pin "3") (pinfunction "3_3") (pintype "passive"))
      (node (ref "JP9") (pin "1") (pinfunction "1_1") (pintype "passive"))
      (node (ref "P1") (pin "A1") (pinfunction "GND_A1") (pintype "bidirectional"))
      (node (ref "P1") (pin "A28") (pinfunction "GND2_A28") (pintype "bidirectional"))
      (node (ref "P1") (pin "A29") (pinfunction "GND3_A29") (pintype "bidirectional"))
      (node (ref "P1") (pin "A30") (pinfunction "GND4_A30") (pintype "bidirectional"))
      (node (ref "P1") (pin "A31") (pinfunction "GND5_A31") (pintype "bidirectional"))
      (node (ref "P1") (pin "A32") (pinfunction "GND6_A32") (pintype "bidirectional"))
      (node (ref "P1") (pin "C1") (pinfunction "GND7_C1") (pintype "bidirectional"))
      (node (ref "P1") (pin "C32") (pinfunction "GND8_C32") (pintype "bidirectional"))
      (node (ref "P2") (pin "A1") (pinfunction "GND_A1") (pintype "bidirectional"))
      (node (ref "P2") (pin "A28") (pinfunction "GND2_A28") (pintype "bidirectional"))
      (node (ref "P2") (pin "A29") (pinfunction "GND3_A29") (pintype "bidirectional"))
      (node (ref "P2") (pin "A30") (pinfunction "GND4_A30") (pintype "bidirectional"))
      (node (ref "P2") (pin "A31") (pinfunction "GND5_A31") (pintype "bidirectional"))
      (node (ref "P2") (pin "A32") (pinfunction "GND6_A32") (pintype "bidirectional"))
      (node (ref "P2") (pin "C1") (pinfunction "GND7_C1") (pintype "bidirectional"))
      (node (ref "P2") (pin "C32") (pinfunction "GND8_C32") (pintype "bidirectional"))
      (node (ref "P3") (pin "A1") (pinfunction "GND_A1") (pintype "bidirectional"))
      (node (ref "P3") (pin "A28") (pinfunction "GND2_A28") (pintype "bidirectional"))
      (node (ref "P3") (pin "A29") (pinfunction "GND3_A29") (pintype "bidirectional"))
      (node (ref "P3") (pin "A30") (pinfunction "GND4_A30") (pintype "bidirectional"))
      (node (ref "P3") (pin "A31") (pinfunction "GND5_A31") (pintype "bidirectional"))
      (node (ref "P3") (pin "A32") (pinfunction "GND6_A32") (pintype "bidirectional"))
      (node (ref "P3") (pin "C1") (pinfunction "GND7_C1") (pintype "bidirectional"))
      (node (ref "P3") (pin "C32") (pinfunction "GND8_C32") (pintype "bidirectional"))
      (node (ref "P4") (pin "A1") (pinfunction "GND_A1") (pintype "bidirectional"))
      (node (ref "P4") (pin "A28") (pinfunction "GND2_A28") (pintype "bidirectional"))
      (node (ref "P4") (pin "A29") (pinfunction "GND3_A29") (pintype "bidirectional"))
      (node (ref "P4") (pin "A30") (pinfunction "GND4_A30") (pintype "bidirectional"))
      (node (ref "P4") (pin "A31") (pinfunction "GND5_A31") (pintype "bidirectional"))
      (node (ref "P4") (pin "A32") (pinfunction "GND6_A32") (pintype "bidirectional"))
      (node (ref "P4") (pin "C1") (pinfunction "GND7_C1") (pintype "bidirectional"))
      (node (ref "P4") (pin "C32") (pinfunction "GND8_C32") (pintype "bidirectional"))
      (node (ref "SLOT3") (pin "Z") (pinfunction "GND_Z") (pintype "bidirectional"))
      (node (ref "SLOT5") (pin "Z") (pinfunction "GND_Z") (pintype "bidirectional"))
      (node (ref "SLOT6.1") (pin "17") (pinfunction "GND_17") (pintype "bidirectional"))
      (node (ref "SLOT6.2") (pin "17") (pinfunction "GND_17") (pintype "bidirectional"))
      (node (ref "SLOT6.3") (pin "17") (pinfunction "GND_17") (pintype "bidirectional"))
      (node (ref "SLOT7") (pin "Z") (pinfunction "GND_Z") (pintype "bidirectional"))
    )
    (net (code "47") (name "I2SCL") (class "Default")
      (node (ref "P1") (pin "A14") (pinfunction "I2CSCL_A14") (pintype "bidirectional"))
      (node (ref "P2") (pin "A14") (pinfunction "I2CSCL_A14") (pintype "bidirectional"))
      (node (ref "P3") (pin "A14") (pinfunction "I2CSCL_A14") (pintype "bidirectional"))
      (node (ref "P4") (pin "A14") (pinfunction "I2CSCL_A14") (pintype "bidirectional"))
    )
    (net (code "48") (name "I2SDA") (class "Default")
      (node (ref "P1") (pin "A13") (pinfunction "I2CSDA_A13") (pintype "bidirectional"))
      (node (ref "P2") (pin "A13") (pinfunction "I2CSDA_A13") (pintype "bidirectional"))
      (node (ref "P3") (pin "A13") (pinfunction "I2CSDA_A13") (pintype "bidirectional"))
      (node (ref "P4") (pin "A13") (pinfunction "I2CSDA_A13") (pintype "bidirectional"))
    )
    (net (code "49") (name "NOEXEC") (class "Default")
      (node (ref "P1") (pin "A10") (pinfunction "NOEXEC_A10") (pintype "bidirectional"))
      (node (ref "P2") (pin "A10") (pinfunction "NOEXEC_A10") (pintype "bidirectional"))
      (node (ref "P3") (pin "A10") (pinfunction "NOEXEC_A10") (pintype "bidirectional"))
      (node (ref "P4") (pin "A10") (pinfunction "NOEXEC_A10") (pintype "bidirectional"))
    )
    (net (code "50") (name "NOTMAPD") (class "Default")
      (node (ref "P1") (pin "A11") (pinfunction "NOTMAPD_A11") (pintype "bidirectional"))
      (node (ref "P2") (pin "A11") (pinfunction "NOTMAPD_A11") (pintype "bidirectional"))
      (node (ref "P3") (pin "A11") (pinfunction "NOTMAPD_A11") (pintype "bidirectional"))
      (node (ref "P4") (pin "A11") (pinfunction "NOTMAPD_A11") (pintype "bidirectional"))
    )
    (net (code "51") (name "Net-(IC1C-O)") (class "Default")
      (node (ref "IC1") (pin "6") (pinfunction "O_6") (pintype "output"))
      (node (ref "IC6") (pin "1") (pinfunction "I0_1") (pintype "input"))
    )
    (net (code "52") (name "Net-(IC1D-O)") (class "Default")
      (node (ref "IC1") (pin "8") (pinfunction "O_8") (pintype "output"))
      (node (ref "IC6") (pin "13") (pinfunction "I1_13") (pintype "input"))
    )
    (net (code "53") (name "Net-(IC1E-O)") (class "Default")
      (node (ref "IC1") (pin "10") (pinfunction "O_10") (pintype "output"))
      (node (ref "IC6") (pin "10") (pinfunction "I1_10") (pintype "input"))
    )
    (net (code "54") (name "Net-(IC4A-G2A)") (class "Default")
      (node (ref "IC4") (pin "4") (pinfunction "G2A_4") (pintype "input"))
      (node (ref "JP16") (pin "2") (pinfunction "2_2") (pintype "passive"))
    )
    (net (code "55") (name "Net-(IC5A-G2B)") (class "Default")
      (node (ref "IC5") (pin "5") (pinfunction "G2B_5") (pintype "input"))
      (node (ref "JP15") (pin "2") (pinfunction "2_2") (pintype "passive"))
    )
    (net (code "56") (name "Net-(IC5A-Y2)") (class "Default")
      (node (ref "IC5") (pin "13") (pinfunction "Y2_13") (pintype "output"))
      (node (ref "JP11") (pin "1") (pinfunction "1_1") (pintype "passive"))
    )
    (net (code "57") (name "Net-(IC5A-Y3)") (class "Default")
      (node (ref "IC5") (pin "12") (pinfunction "Y3_12") (pintype "output"))
      (node (ref "JP10") (pin "1") (pinfunction "1_1") (pintype "passive"))
    )
    (net (code "58") (name "Net-(IC5A-Y4)") (class "Default")
      (node (ref "IC5") (pin "11") (pinfunction "Y4_11") (pintype "output"))
      (node (ref "JP11") (pin "3") (pinfunction "3_3") (pintype "passive"))
    )
    (net (code "59") (name "Net-(IC5A-Y5)") (class "Default")
      (node (ref "IC5") (pin "10") (pinfunction "Y5_10") (pintype "output"))
      (node (ref "JP10") (pin "3") (pinfunction "3_3") (pintype "passive"))
    )
    (net (code "60") (name "Net-(IC7A-OE)") (class "Default")
      (node (ref "IC7") (pin "1") (pinfunction "OE_1") (pintype "input"))
      (node (ref "IC7") (pin "10") (pinfunction "OE_10") (pintype "input"))
      (node (ref "IC7") (pin "13") (pinfunction "OE_13") (pintype "input"))
      (node (ref "IC7") (pin "4") (pinfunction "OE_4") (pintype "input"))
      (node (ref "IC8") (pin "1") (pinfunction "OE_1") (pintype "input"))
      (node (ref "IC8") (pin "4") (pinfunction "OE_4") (pintype "input"))
      (node (ref "JP9") (pin "2") (pinfunction "2_2") (pintype "passive"))
    )
    (net (code "61") (name "Net-(SLOT3-DMA_OUT)") (class "Default")
      (node (ref "SLOT3") (pin "24") (pinfunction "DMA_OUT_24") (pintype "bidirectional"))
      (node (ref "SLOT5") (pin "Y") (pinfunction "DMA_IN_Y") (pintype "bidirectional"))
    )
    (net (code "62") (name "Net-(SLOT3-INT_OUT)") (class "Default")
      (node (ref "SLOT3") (pin "23") (pinfunction "INT_OUT_23") (pintype "bidirectional"))
      (node (ref "SLOT5") (pin "X") (pinfunction "INT_IN_X") (pintype "bidirectional"))
    )
    (net (code "63") (name "Net-(SLOT5-DMA_OUT)") (class "Default")
      (node (ref "SLOT5") (pin "24") (pinfunction "DMA_OUT_24") (pintype "bidirectional"))
      (node (ref "SLOT7") (pin "Y") (pinfunction "DMA_IN_Y") (pintype "bidirectional"))
    )
    (net (code "64") (name "Net-(SLOT5-INT_OUT)") (class "Default")
      (node (ref "SLOT5") (pin "23") (pinfunction "INT_OUT_23") (pintype "bidirectional"))
      (node (ref "SLOT7") (pin "X") (pinfunction "INT_IN_X") (pintype "bidirectional"))
    )
    (net (code "65") (name "Net-(SLOT6.3-*PHI1,{slash}MREQ)") (class "Default")
      (node (ref "JP3") (pin "2") (pinfunction "2_2") (pintype "passive"))
      (node (ref "SLOT6.3") (pin "23") (pinfunction "*PHI1,/MREQ_23") (pintype "bidirectional"))
    )
    (net (code "66") (name "Net-(SLOT6.3-*PHI2,{slash}M1)") (class "Default")
      (node (ref "JP2") (pin "2") (pinfunction "2_2") (pintype "passive"))
      (node (ref "SLOT6.3") (pin "19") (pinfunction "*PHI2,/M1_19") (pintype "bidirectional"))
    )
    (net (code "67") (name "Net-(SLOT6.3-*RDY,{slash}RD)") (class "Default")
      (node (ref "JP5") (pin "2") (pinfunction "2_2") (pintype "passive"))
      (node (ref "SLOT6.3") (pin "25") (pinfunction "*RDY,/RD_25") (pintype "bidirectional"))
    )
    (net (code "68") (name "Net-(SLOT6.3-*R{slash}-W,{slash}WR)") (class "Default")
      (node (ref "JP4") (pin "2") (pinfunction "2_2") (pintype "passive"))
      (node (ref "SLOT6.3") (pin "24") (pinfunction "*R/-W,/WR_24") (pintype "bidirectional"))
    )
    (net (code "69") (name "Net-(SLOT6.3-*SYNC,{slash}IOREQ)") (class "Default")
      (node (ref "JP6") (pin "2") (pinfunction "2_2") (pintype "passive"))
      (node (ref "SLOT6.3") (pin "26") (pinfunction "*SYNC,/IOREQ_26") (pintype "bidirectional"))
    )
    (net (code "70") (name "Net-(SLOT6.3-*{slash}NMI,USER1)") (class "Default")
      (node (ref "JP7") (pin "2") (pinfunction "2_2") (pintype "passive"))
      (node (ref "SLOT6.3") (pin "37") (pinfunction "*/NMI,USER1_37") (pintype "bidirectional"))
    )
    (net (code "71") (name "RDY") (class "Default")
      (node (ref "JP5") (pin "1") (pinfunction "1_1") (pintype "passive"))
      (node (ref "P1") (pin "A26") (pinfunction "RDY_A26") (pintype "bidirectional"))
      (node (ref "P2") (pin "A26") (pinfunction "RDY_A26") (pintype "bidirectional"))
      (node (ref "P3") (pin "A26") (pinfunction "RDY_A26") (pintype "bidirectional"))
      (node (ref "P4") (pin "A26") (pinfunction "RDY_A26") (pintype "bidirectional"))
      (node (ref "SLOT3") (pin "21") (pinfunction "RDY_21") (pintype "bidirectional"))
      (node (ref "SLOT5") (pin "21") (pinfunction "RDY_21") (pintype "bidirectional"))
      (node (ref "SLOT7") (pin "21") (pinfunction "RDY_21") (pintype "bidirectional"))
    )
    (net (code "72") (name "RX") (class "Default")
      (node (ref "SLOT6.1") (pin "36") (pinfunction "RX_36") (pintype "bidirectional"))
      (node (ref "SLOT6.2") (pin "36") (pinfunction "RX_36") (pintype "bidirectional"))
      (node (ref "SLOT6.3") (pin "36") (pinfunction "RX_36") (pintype "bidirectional"))
    )
    (net (code "73") (name "R{slash}-W") (class "Default")
      (node (ref "IC1") (pin "5") (pinfunction "I_5") (pintype "input"))
      (node (ref "IC6") (pin "12") (pinfunction "I0_12") (pintype "input"))
      (node (ref "IC6") (pin "5") (pinfunction "I1_5") (pintype "input"))
      (node (ref "IC6") (pin "9") (pinfunction "I0_9") (pintype "input"))
      (node (ref "JP4") (pin "1") (pinfunction "1_1") (pintype "passive"))
      (node (ref "P1") (pin "C25") (pinfunction "R/-W_C25") (pintype "bidirectional"))
      (node (ref "P2") (pin "C25") (pinfunction "R/-W_C25") (pintype "bidirectional"))
      (node (ref "P3") (pin "C25") (pinfunction "R/-W_C25") (pintype "bidirectional"))
      (node (ref "P4") (pin "C25") (pinfunction "R/-W_C25") (pintype "bidirectional"))
      (node (ref "SLOT3") (pin "18") (pinfunction "R/-W_18") (pintype "bidirectional"))
      (node (ref "SLOT5") (pin "18") (pinfunction "R/-W_18") (pintype "bidirectional"))
      (node (ref "SLOT7") (pin "18") (pinfunction "R/-W_18") (pintype "bidirectional"))
    )
    (net (code "74") (name "SLOT0DEV") (class "Default")
      (node (ref "IC4") (pin "15") (pinfunction "Y0_15") (pintype "output"))
    )
    (net (code "75") (name "SLOT3DEV") (class "Default")
      (node (ref "IC4") (pin "12") (pinfunction "Y3_12") (pintype "output"))
      (node (ref "SLOT3") (pin "K") (pinfunction "/DEVSELECT_K") (pintype "bidirectional"))
    )
    (net (code "76") (name "SLOT5DEV") (class "Default")
      (node (ref "IC4") (pin "10") (pinfunction "Y5_10") (pintype "output"))
      (node (ref "SLOT5") (pin "K") (pinfunction "/DEVSELECT_K") (pintype "bidirectional"))
    )
    (net (code "77") (name "SLOT6DEV") (class "Default")
      (node (ref "IC4") (pin "9") (pinfunction "Y6_9") (pintype "output"))
    )
    (net (code "78") (name "SLOT7DEV") (class "Default")
      (node (ref "IC4") (pin "7") (pinfunction "Y7_7") (pintype "output"))
      (node (ref "SLOT7") (pin "K") (pinfunction "/DEVSELECT_K") (pintype "bidirectional"))
    )
    (net (code "79") (name "SYNC") (class "Default")
      (node (ref "IC1") (pin "3") (pinfunction "I_3") (pintype "input"))
      (node (ref "JP6") (pin "1") (pinfunction "1_1") (pintype "passive"))
      (node (ref "P1") (pin "C24") (pinfunction "SYNC_C24") (pintype "bidirectional"))
      (node (ref "P2") (pin "C24") (pinfunction "SYNC_C24") (pintype "bidirectional"))
      (node (ref "P3") (pin "C24") (pinfunction "SYNC_C24") (pintype "bidirectional"))
      (node (ref "P4") (pin "C24") (pinfunction "SYNC_C24") (pintype "bidirectional"))
      (node (ref "SLOT3") (pin "19") (pinfunction "SYNC_19") (pintype "bidirectional"))
      (node (ref "SLOT5") (pin "19") (pinfunction "SYNC_19") (pintype "bidirectional"))
      (node (ref "SLOT7") (pin "19") (pinfunction "SYNC_19") (pintype "bidirectional"))
    )
    (net (code "80") (name "TX") (class "Default")
      (node (ref "SLOT6.1") (pin "35") (pinfunction "TX_35") (pintype "bidirectional"))
      (node (ref "SLOT6.2") (pin "35") (pinfunction "TX_35") (pintype "bidirectional"))
      (node (ref "SLOT6.3") (pin "35") (pinfunction "TX_35") (pintype "bidirectional"))
    )
    (net (code "81") (name "USER1") (class "Default")
      (node (ref "JP7") (pin "3") (pinfunction "3_3") (pintype "passive"))
      (node (ref "SLOT6.1") (pin "37") (pinfunction "*/NMI,USER1_37") (pintype "bidirectional"))
      (node (ref "SLOT6.2") (pin "37") (pinfunction "*/NMI,USER1_37") (pintype "bidirectional"))
    )
    (net (code "82") (name "USER2") (class "Default")
      (node (ref "SLOT6.1") (pin "38") (pinfunction "EX1/USER2_38") (pintype "bidirectional"))
      (node (ref "SLOT6.2") (pin "38") (pinfunction "EX1/USER2_38") (pintype "bidirectional"))
      (node (ref "SLOT6.3") (pin "38") (pinfunction "EX1/USER2_38") (pintype "bidirectional"))
    )
    (net (code "83") (name "USER3") (class "Default")
      (node (ref "SLOT6.1") (pin "39") (pinfunction "EX2/USER3_39") (pintype "bidirectional"))
      (node (ref "SLOT6.2") (pin "39") (pinfunction "EX2/USER3_39") (pintype "bidirectional"))
      (node (ref "SLOT6.3") (pin "39") (pinfunction "EX2/USER3_39") (pintype "bidirectional"))
    )
    (net (code "84") (name "USER4") (class "Default")
      (node (ref "SLOT6.1") (pin "40") (pinfunction "USER4_40") (pintype "bidirectional"))
      (node (ref "SLOT6.2") (pin "40") (pinfunction "USER4_40") (pintype "bidirectional"))
      (node (ref "SLOT6.3") (pin "40") (pinfunction "USER4_40") (pintype "bidirectional"))
    )
    (net (code "85") (name "VBUF") (class "Default")
      (node (ref "P1") (pin "A2") (pinfunction "VBUF_A2") (pintype "bidirectional"))
      (node (ref "P2") (pin "A2") (pinfunction "VBUF_A2") (pintype "bidirectional"))
      (node (ref "P3") (pin "A2") (pinfunction "VBUF_A2") (pintype "bidirectional"))
      (node (ref "P4") (pin "A2") (pinfunction "VBUF_A2") (pintype "bidirectional"))
    )
    (net (code "86") (name "VCC") (class "Default")
      (node (ref "C10") (pin "1") (pinfunction "1_1") (pintype "passive"))
      (node (ref "C11") (pin "1") (pinfunction "1_1") (pintype "passive"))
      (node (ref "C12") (pin "1") (pinfunction "1_1") (pintype "passive"))
      (node (ref "C13") (pin "+") (pinfunction "+_+") (pintype "passive"))
      (node (ref "C14") (pin "+") (pinfunction "+_+") (pintype "passive"))
      (node (ref "C15") (pin "+") (pinfunction "+_+") (pintype "passive"))
      (node (ref "C16") (pin "1") (pinfunction "1_1") (pintype "passive"))
      (node (ref "C17") (pin "+") (pinfunction "+_+") (pintype "passive"))
      (node (ref "C18") (pin "+") (pinfunction "+_+") (pintype "passive"))
      (node (ref "C2") (pin "1") (pinfunction "1_1") (pintype "passive"))
      (node (ref "C3") (pin "+") (pinfunction "+_+") (pintype "passive"))
      (node (ref "C5") (pin "+") (pinfunction "+_+") (pintype "passive"))
      (node (ref "C7") (pin "1") (pinfunction "1_1") (pintype "passive"))
      (node (ref "C8") (pin "1") (pinfunction "1_1") (pintype "passive"))
      (node (ref "C9") (pin "1") (pinfunction "1_1") (pintype "passive"))
      (node (ref "IC2") (pin "6") (pinfunction "G1_6") (pintype "input"))
      (node (ref "IC3") (pin "6") (pinfunction "G1_6") (pintype "input"))
      (node (ref "J1") (pin "4") (pinfunction "4_4") (pintype "passive"))
      (node (ref "P1") (pin "C2") (pinfunction "VCC_C2") (pintype "bidirectional"))
      (node (ref "P1") (pin "C3") (pinfunction "VCC2_C3") (pintype "bidirectional"))
      (node (ref "P2") (pin "C2") (pinfunction "VCC_C2") (pintype "bidirectional"))
      (node (ref "P2") (pin "C3") (pinfunction "VCC2_C3") (pintype "bidirectional"))
      (node (ref "P3") (pin "C2") (pinfunction "VCC_C2") (pintype "bidirectional"))
      (node (ref "P3") (pin "C3") (pinfunction "VCC2_C3") (pintype "bidirectional"))
      (node (ref "P4") (pin "C2") (pinfunction "VCC_C2") (pintype "bidirectional"))
      (node (ref "P4") (pin "C3") (pinfunction "VCC2_C3") (pintype "bidirectional"))
      (node (ref "SLOT3") (pin "25") (pinfunction "5V_25") (pintype "bidirectional"))
      (node (ref "SLOT5") (pin "25") (pinfunction "5V_25") (pintype "bidirectional"))
      (node (ref "SLOT6.1") (pin "18") (pinfunction "VCC_18") (pintype "bidirectional"))
      (node (ref "SLOT6.2") (pin "18") (pinfunction "VCC_18") (pintype "bidirectional"))
      (node (ref "SLOT6.3") (pin "18") (pinfunction "VCC_18") (pintype "bidirectional"))
      (node (ref "SLOT7") (pin "25") (pinfunction "5V_25") (pintype "bidirectional"))
    )
    (net (code "87") (name "VCC33") (class "Default")
      (node (ref "C1") (pin "+") (pinfunction "+_+") (pintype "passive"))
      (node (ref "C4") (pin "+") (pinfunction "+_+") (pintype "passive"))
      (node (ref "C6") (pin "+") (pinfunction "+_+") (pintype "passive"))
      (node (ref "P1") (pin "A9") (pinfunction "VCC33_A9") (pintype "bidirectional"))
      (node (ref "P2") (pin "A9") (pinfunction "VCC33_A9") (pintype "bidirectional"))
      (node (ref "P3") (pin "A9") (pinfunction "VCC33_A9") (pintype "bidirectional"))
      (node (ref "P4") (pin "A9") (pinfunction "VCC33_A9") (pintype "bidirectional"))
    )
    (net (code "88") (name "WPROT") (class "Default")
      (node (ref "P1") (pin "A12") (pinfunction "WPROT_A12") (pintype "bidirectional"))
      (node (ref "P2") (pin "A12") (pinfunction "WPROT_A12") (pintype "bidirectional"))
      (node (ref "P3") (pin "A12") (pinfunction "WPROT_A12") (pintype "bidirectional"))
      (node (ref "P4") (pin "A12") (pinfunction "WPROT_A12") (pintype "bidirectional"))
    )
    (net (code "89") (name "unconnected-(IC2A-Y1-Pad14)") (class "Default")
      (node (ref "IC2") (pin "14") (pinfunction "Y1_14") (pintype "output"))
    )
    (net (code "90") (name "unconnected-(IC2A-Y3-Pad12)") (class "Default")
      (node (ref "IC2") (pin "12") (pinfunction "Y3_12") (pintype "output"))
    )
    (net (code "91") (name "unconnected-(IC2A-Y7-Pad7)") (class "Default")
      (node (ref "IC2") (pin "7") (pinfunction "Y7_7") (pintype "output"))
    )
    (net (code "92") (name "unconnected-(IC3A-Y1-Pad14)") (class "Default")
      (node (ref "IC3") (pin "14") (pinfunction "Y1_14") (pintype "output"))
    )
    (net (code "93") (name "unconnected-(IC3A-Y4-Pad11)") (class "Default")
      (node (ref "IC3") (pin "11") (pinfunction "Y4_11") (pintype "output"))
    )
    (net (code "94") (name "unconnected-(IC4A-Y1-Pad14)") (class "Default")
      (node (ref "IC4") (pin "14") (pinfunction "Y1_14") (pintype "output"))
    )
    (net (code "95") (name "unconnected-(IC4A-Y2-Pad13)") (class "Default")
      (node (ref "IC4") (pin "13") (pinfunction "Y2_13") (pintype "output"))
    )
    (net (code "96") (name "unconnected-(IC4A-Y4-Pad11)") (class "Default")
      (node (ref "IC4") (pin "11") (pinfunction "Y4_11") (pintype "output"))
    )
    (net (code "97") (name "unconnected-(IC5A-Y0-Pad15)") (class "Default")
      (node (ref "IC5") (pin "15") (pinfunction "Y0_15") (pintype "output"))
    )
    (net (code "98") (name "unconnected-(IC5A-Y1-Pad14)") (class "Default")
      (node (ref "IC5") (pin "14") (pinfunction "Y1_14") (pintype "output"))
    )
    (net (code "99") (name "unconnected-(IC5A-Y6-Pad9)") (class "Default")
      (node (ref "IC5") (pin "9") (pinfunction "Y6_9") (pintype "output"))
    )
    (net (code "100") (name "unconnected-(IC5A-Y7-Pad7)") (class "Default")
      (node (ref "IC5") (pin "7") (pinfunction "Y7_7") (pintype "output"))
    )
    (net (code "101") (name "unconnected-(SLOT3--5V-PadR)") (class "Default")
      (node (ref "SLOT3") (pin "R") (pinfunction "-5V_R") (pintype "bidirectional"))
    )
    (net (code "102") (name "unconnected-(SLOT3--12V-PadS)") (class "Default")
      (node (ref "SLOT3") (pin "S") (pinfunction "-12V_S") (pintype "bidirectional"))
    )
    (net (code "103") (name "unconnected-(SLOT3-DMA_IN-PadY)") (class "Default")
      (node (ref "SLOT3") (pin "Y") (pinfunction "DMA_IN_Y") (pintype "bidirectional"))
    )
    (net (code "104") (name "unconnected-(SLOT3-INT_IN-PadX)") (class "Default")
      (node (ref "SLOT3") (pin "X") (pinfunction "INT_IN_X") (pintype "bidirectional"))
    )
    (net (code "105") (name "unconnected-(SLOT3-{slash}INH-PadT)") (class "Default")
      (node (ref "SLOT3") (pin "T") (pinfunction "/INH_T") (pintype "bidirectional"))
    )
    (net (code "106") (name "unconnected-(SLOT5--5V-PadR)") (class "Default")
      (node (ref "SLOT5") (pin "R") (pinfunction "-5V_R") (pintype "bidirectional"))
    )
    (net (code "107") (name "unconnected-(SLOT5--12V-PadS)") (class "Default")
      (node (ref "SLOT5") (pin "S") (pinfunction "-12V_S") (pintype "bidirectional"))
    )
    (net (code "108") (name "unconnected-(SLOT5-{slash}INH-PadT)") (class "Default")
      (node (ref "SLOT5") (pin "T") (pinfunction "/INH_T") (pintype "bidirectional"))
    )
    (net (code "109") (name "unconnected-(SLOT7--5V-PadR)") (class "Default")
      (node (ref "SLOT7") (pin "R") (pinfunction "-5V_R") (pintype "bidirectional"))
    )
    (net (code "110") (name "unconnected-(SLOT7--12V-PadS)") (class "Default")
      (node (ref "SLOT7") (pin "S") (pinfunction "-12V_S") (pintype "bidirectional"))
    )
    (net (code "111") (name "unconnected-(SLOT7-DMA_OUT-Pad24)") (class "Default")
      (node (ref "SLOT7") (pin "24") (pinfunction "DMA_OUT_24") (pintype "bidirectional"))
    )
    (net (code "112") (name "unconnected-(SLOT7-INT_OUT-Pad23)") (class "Default")
      (node (ref "SLOT7") (pin "23") (pinfunction "INT_OUT_23") (pintype "bidirectional"))
    )
    (net (code "113") (name "unconnected-(SLOT7-{slash}INH-PadT)") (class "Default")
      (node (ref "SLOT7") (pin "T") (pinfunction "/INH_T") (pintype "bidirectional"))
    )
    (net (code "114") (name "{slash}BANK0") (class "Default")
      (node (ref "IC2") (pin "15") (pinfunction "Y0_15") (pintype "output"))
      (node (ref "JP14") (pin "1") (pinfunction "1_1") (pintype "passive"))
      (node (ref "JP15") (pin "1") (pinfunction "1_1") (pintype "passive"))
    )
    (net (code "115") (name "{slash}BANK2") (class "Default")
      (node (ref "IC2") (pin "13") (pinfunction "Y2_13") (pintype "output"))
      (node (ref "JP15") (pin "3") (pinfunction "3_3") (pintype "passive"))
    )
    (net (code "116") (name "{slash}BANK4") (class "Default")
      (node (ref "IC2") (pin "11") (pinfunction "Y4_11") (pintype "output"))
    )
    (net (code "117") (name "{slash}BANK4_Q") (class "Default")
      (node (ref "IC6") (pin "8") (pinfunction "O_8") (pintype "output"))
      (node (ref "SLOT6.1") (pin "23") (pinfunction "*PHI1,/MREQ_23") (pintype "bidirectional"))
    )
    (net (code "118") (name "{slash}BANK5") (class "Default")
      (node (ref "IC2") (pin "10") (pinfunction "Y5_10") (pintype "output"))
    )
    (net (code "119") (name "{slash}BANK6") (class "Default")
      (node (ref "IC2") (pin "9") (pinfunction "Y6_9") (pintype "output"))
      (node (ref "JP14") (pin "3") (pinfunction "3_3") (pintype "passive"))
    )
    (net (code "120") (name "{slash}BE") (class "Default")
      (node (ref "IC8") (pin "3") (pinfunction "O_3") (pintype "tri_state"))
      (node (ref "P1") (pin "A8") (pinfunction "/BE_A8") (pintype "bidirectional"))
      (node (ref "P2") (pin "A8") (pinfunction "/BE_A8") (pintype "bidirectional"))
      (node (ref "P3") (pin "A8") (pinfunction "/BE_A8") (pintype "bidirectional"))
      (node (ref "P4") (pin "A8") (pinfunction "/BE_A8") (pintype "bidirectional"))
    )
    (net (code "121") (name "{slash}DMA") (class "Default")
      (node (ref "JP9") (pin "3") (pinfunction "3_3") (pintype "passive"))
      (node (ref "SLOT3") (pin "22") (pinfunction "/DMA_22") (pintype "bidirectional"))
      (node (ref "SLOT5") (pin "22") (pinfunction "/DMA_22") (pintype "bidirectional"))
      (node (ref "SLOT7") (pin "22") (pinfunction "/DMA_22") (pintype "bidirectional"))
    )
    (net (code "122") (name "{slash}EXTIO") (class "Default")
      (node (ref "P1") (pin "A5") (pinfunction "/EXTIO_A5") (pintype "bidirectional"))
      (node (ref "P2") (pin "A5") (pinfunction "/EXTIO_A5") (pintype "bidirectional"))
      (node (ref "P3") (pin "A5") (pinfunction "/EXTIO_A5") (pintype "bidirectional"))
      (node (ref "P4") (pin "A5") (pinfunction "/EXTIO_A5") (pintype "bidirectional"))
    )
    (net (code "123") (name "{slash}IOINH") (class "Default")
      (node (ref "JP8") (pin "1") (pinfunction "1_1") (pintype "passive"))
      (node (ref "P1") (pin "A4") (pinfunction "/IOINH_A4") (pintype "bidirectional"))
      (node (ref "P2") (pin "A4") (pinfunction "/IOINH_A4") (pintype "bidirectional"))
      (node (ref "P3") (pin "A4") (pinfunction "/IOINH_A4") (pintype "bidirectional"))
      (node (ref "P4") (pin "A4") (pinfunction "/IOINH_A4") (pintype "bidirectional"))
    )
    (net (code "124") (name "{slash}IOSEL") (class "Default")
      (node (ref "JP16") (pin "3") (pinfunction "3_3") (pintype "passive"))
      (node (ref "JP17") (pin "2") (pinfunction "2_2") (pintype "passive"))
      (node (ref "P1") (pin "A7") (pinfunction "/IOSEL_A7") (pintype "bidirectional"))
      (node (ref "P2") (pin "A7") (pinfunction "/IOSEL_A7") (pintype "bidirectional"))
      (node (ref "P3") (pin "A7") (pinfunction "/IOSEL_A7") (pintype "bidirectional"))
      (node (ref "P4") (pin "A7") (pinfunction "/IOSEL_A7") (pintype "bidirectional"))
    )
    (net (code "125") (name "{slash}IOSTROBE") (class "Default")
      (node (ref "JP10") (pin "2") (pinfunction "2_2") (pintype "passive"))
      (node (ref "SLOT3") (pin "20") (pinfunction "/IOSTROBE_20") (pintype "bidirectional"))
      (node (ref "SLOT5") (pin "20") (pinfunction "/IOSTROBE_20") (pintype "bidirectional"))
      (node (ref "SLOT7") (pin "20") (pinfunction "/IOSTROBE_20") (pintype "bidirectional"))
    )
    (net (code "126") (name "{slash}IRQ") (class "Default")
      (node (ref "P1") (pin "A24") (pinfunction "/IRQ_A24") (pintype "bidirectional"))
      (node (ref "P2") (pin "A24") (pinfunction "/IRQ_A24") (pintype "bidirectional"))
      (node (ref "P3") (pin "A24") (pinfunction "/IRQ_A24") (pintype "bidirectional"))
      (node (ref "P4") (pin "A24") (pinfunction "/IRQ_A24") (pintype "bidirectional"))
      (node (ref "SLOT3") (pin "V") (pinfunction "/IRQ_V") (pintype "bidirectional"))
      (node (ref "SLOT5") (pin "V") (pinfunction "/IRQ_V") (pintype "bidirectional"))
      (node (ref "SLOT6.1") (pin "22") (pinfunction "/IRQ_22") (pintype "bidirectional"))
      (node (ref "SLOT6.2") (pin "22") (pinfunction "/IRQ_22") (pintype "bidirectional"))
      (node (ref "SLOT6.3") (pin "22") (pinfunction "/IRQ_22") (pintype "bidirectional"))
      (node (ref "SLOT7") (pin "V") (pinfunction "/IRQ_V") (pintype "bidirectional"))
    )
    (net (code "127") (name "{slash}M1") (class "Default")
      (node (ref "IC1") (pin "4") (pinfunction "O_4") (pintype "output"))
      (node (ref "JP2") (pin "3") (pinfunction "3_3") (pintype "passive"))
      (node (ref "SLOT6.1") (pin "19") (pinfunction "*PHI2,/M1_19") (pintype "bidirectional"))
      (node (ref "SLOT6.2") (pin "19") (pinfunction "*PHI2,/M1_19") (pintype "bidirectional"))
    )
    (net (code "128") (name "{slash}MEMSEL") (class "Default")
      (node (ref "IC2") (pin "5") (pinfunction "G2B_5") (pintype "input"))
      (node (ref "IC8") (pin "6") (pinfunction "O_6") (pintype "tri_state"))
      (node (ref "P1") (pin "A6") (pinfunction "/MEMSEL_A6") (pintype "bidirectional"))
      (node (ref "P2") (pin "A6") (pinfunction "/MEMSEL_A6") (pintype "bidirectional"))
      (node (ref "P3") (pin "A6") (pinfunction "/MEMSEL_A6") (pintype "bidirectional"))
      (node (ref "P4") (pin "A6") (pinfunction "/MEMSEL_A6") (pintype "bidirectional"))
    )
    (net (code "129") (name "{slash}NMI") (class "Default")
      (node (ref "JP7") (pin "1") (pinfunction "1_1") (pintype "passive"))
      (node (ref "P1") (pin "A23") (pinfunction "/NMI_A23") (pintype "bidirectional"))
      (node (ref "P2") (pin "A23") (pinfunction "/NMI_A23") (pintype "bidirectional"))
      (node (ref "P3") (pin "A23") (pinfunction "/NMI_A23") (pintype "bidirectional"))
      (node (ref "P4") (pin "A23") (pinfunction "/NMI_A23") (pintype "bidirectional"))
      (node (ref "SLOT3") (pin "W") (pinfunction "/NMI_W") (pintype "bidirectional"))
      (node (ref "SLOT5") (pin "W") (pinfunction "/NMI_W") (pintype "bidirectional"))
      (node (ref "SLOT7") (pin "W") (pinfunction "/NMI_W") (pintype "bidirectional"))
    )
    (net (code "130") (name "{slash}RD0") (class "Default")
      (node (ref "IC6") (pin "6") (pinfunction "O_6") (pintype "output"))
      (node (ref "JP5") (pin "3") (pinfunction "3_3") (pintype "passive"))
      (node (ref "SLOT6.1") (pin "25") (pinfunction "*RDY,/RD_25") (pintype "bidirectional"))
      (node (ref "SLOT6.2") (pin "25") (pinfunction "*RDY,/RD_25") (pintype "bidirectional"))
    )
    (net (code "131") (name "{slash}RES") (class "Default")
      (node (ref "P1") (pin "A27") (pinfunction "/RES_A27") (pintype "bidirectional"))
      (node (ref "P2") (pin "A27") (pinfunction "/RES_A27") (pintype "bidirectional"))
      (node (ref "P3") (pin "A27") (pinfunction "/RES_A27") (pintype "bidirectional"))
      (node (ref "P4") (pin "A27") (pinfunction "/RES_A27") (pintype "bidirectional"))
      (node (ref "SLOT3") (pin "U") (pinfunction "/RES_U") (pintype "bidirectional"))
      (node (ref "SLOT5") (pin "U") (pinfunction "/RES_U") (pintype "bidirectional"))
      (node (ref "SLOT6.1") (pin "20") (pinfunction "/RES_20") (pintype "bidirectional"))
      (node (ref "SLOT6.2") (pin "20") (pinfunction "/RES_20") (pintype "bidirectional"))
      (node (ref "SLOT6.3") (pin "20") (pinfunction "/RES_20") (pintype "bidirectional"))
      (node (ref "SLOT7") (pin "U") (pinfunction "/RES_U") (pintype "bidirectional"))
    )
    (net (code "132") (name "{slash}SEL6") (class "Default")
      (node (ref "IC1") (pin "11") (pinfunction "I_11") (pintype "input"))
      (node (ref "JP14") (pin "2") (pinfunction "2_2") (pintype "passive"))
      (node (ref "JP3") (pin "3") (pinfunction "3_3") (pintype "passive"))
      (node (ref "SLOT6.2") (pin "23") (pinfunction "*PHI1,/MREQ_23") (pintype "bidirectional"))
    )
    (net (code "133") (name "{slash}SLOT0IO") (class "Default")
      (node (ref "IC3") (pin "15") (pinfunction "Y0_15") (pintype "output"))
      (node (ref "JP16") (pin "1") (pinfunction "1_1") (pintype "passive"))
    )
    (net (code "134") (name "{slash}SLOT2IO") (class "Default")
      (node (ref "IC3") (pin "13") (pinfunction "Y2_13") (pintype "output"))
      (node (ref "JP17") (pin "1") (pinfunction "1_1") (pintype "passive"))
    )
    (net (code "135") (name "{slash}SLOT3IO") (class "Default")
      (node (ref "IC3") (pin "12") (pinfunction "Y3_12") (pintype "output"))
      (node (ref "SLOT3") (pin "1") (pinfunction "/IOSELECT_1") (pintype "bidirectional"))
    )
    (net (code "136") (name "{slash}SLOT4IO_Q") (class "Default")
      (node (ref "IC6") (pin "11") (pinfunction "O_11") (pintype "output"))
      (node (ref "SLOT6.1") (pin "26") (pinfunction "*SYNC,/IOREQ_26") (pintype "bidirectional"))
    )
    (net (code "137") (name "{slash}SLOT5IO") (class "Default")
      (node (ref "IC3") (pin "10") (pinfunction "Y5_10") (pintype "output"))
      (node (ref "SLOT5") (pin "1") (pinfunction "/IOSELECT_1") (pintype "bidirectional"))
    )
    (net (code "138") (name "{slash}SLOT6IO") (class "Default")
      (node (ref "IC1") (pin "9") (pinfunction "I_9") (pintype "input"))
      (node (ref "IC3") (pin "9") (pinfunction "Y6_9") (pintype "output"))
      (node (ref "JP6") (pin "3") (pinfunction "3_3") (pintype "passive"))
      (node (ref "SLOT6.2") (pin "26") (pinfunction "*SYNC,/IOREQ_26") (pintype "bidirectional"))
    )
    (net (code "139") (name "{slash}SLOT7IO") (class "Default")
      (node (ref "IC3") (pin "7") (pinfunction "Y7_7") (pintype "output"))
      (node (ref "SLOT7") (pin "1") (pinfunction "/IOSELECT_1") (pintype "bidirectional"))
    )
    (net (code "140") (name "{slash}SLOTIO") (class "Default")
      (node (ref "IC3") (pin "4") (pinfunction "G2A_4") (pintype "input"))
      (node (ref "JP11") (pin "2") (pinfunction "2_2") (pintype "passive"))
    )
    (net (code "141") (name "{slash}SO") (class "Default")
      (node (ref "P1") (pin "A25") (pinfunction "/SO_A25") (pintype "bidirectional"))
      (node (ref "P2") (pin "A25") (pinfunction "/SO_A25") (pintype "bidirectional"))
      (node (ref "P3") (pin "A25") (pinfunction "/SO_A25") (pintype "bidirectional"))
      (node (ref "P4") (pin "A25") (pinfunction "/SO_A25") (pintype "bidirectional"))
    )
    (net (code "142") (name "{slash}WR0") (class "Default")
      (node (ref "IC6") (pin "3") (pinfunction "O_3") (pintype "output"))
      (node (ref "JP4") (pin "3") (pinfunction "3_3") (pintype "passive"))
      (node (ref "SLOT6.1") (pin "24") (pinfunction "*R/-W,/WR_24") (pintype "bidirectional"))
      (node (ref "SLOT6.2") (pin "24") (pinfunction "*R/-W,/WR_24") (pintype "bidirectional"))
    )
  )
)
